# power_supply_module.net
KiCad netlist of a schematic drawn in EAGLE
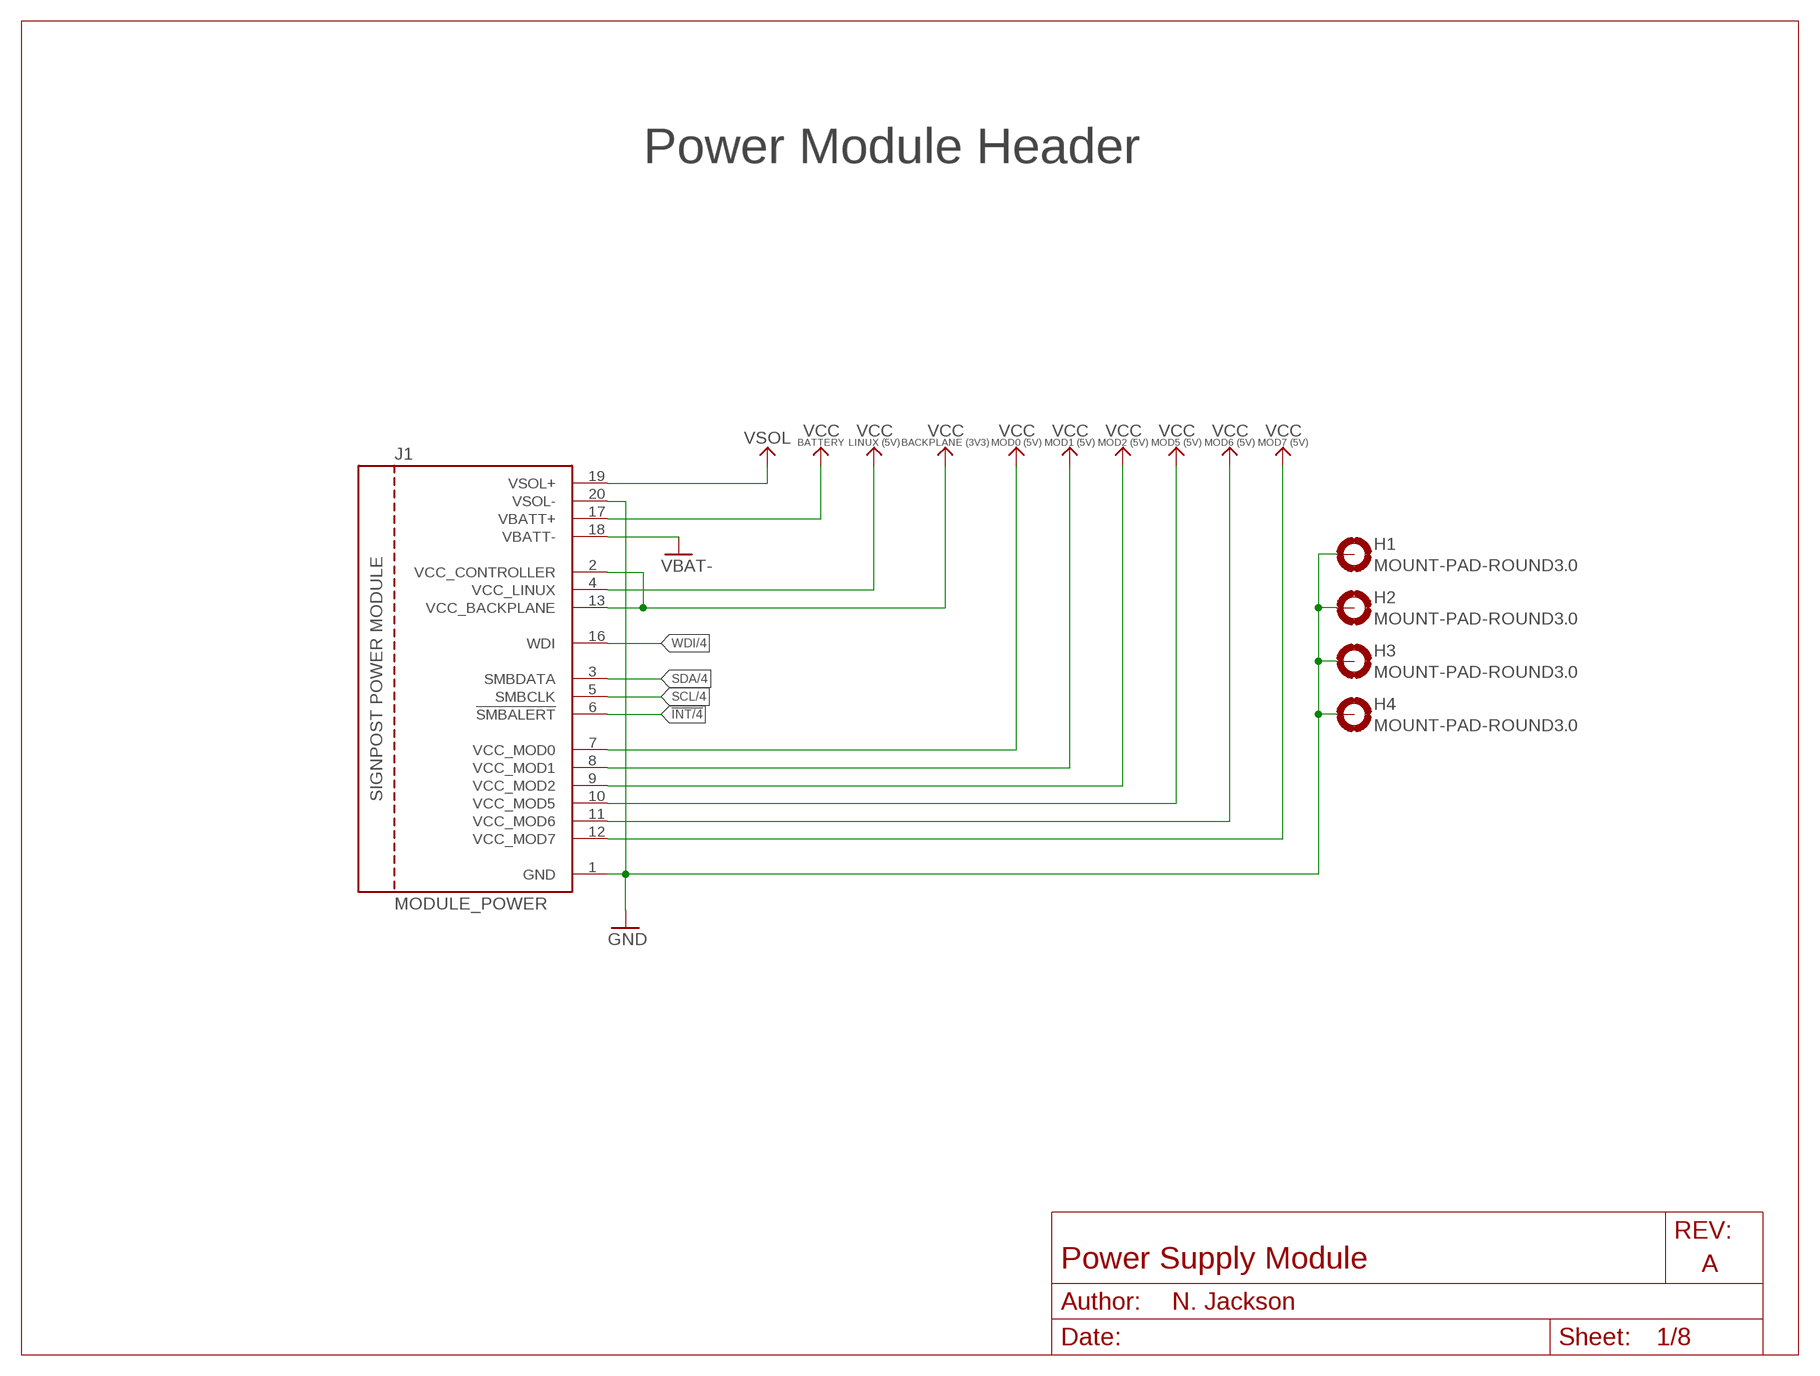
[diagram p0: schematic, sheet 1]
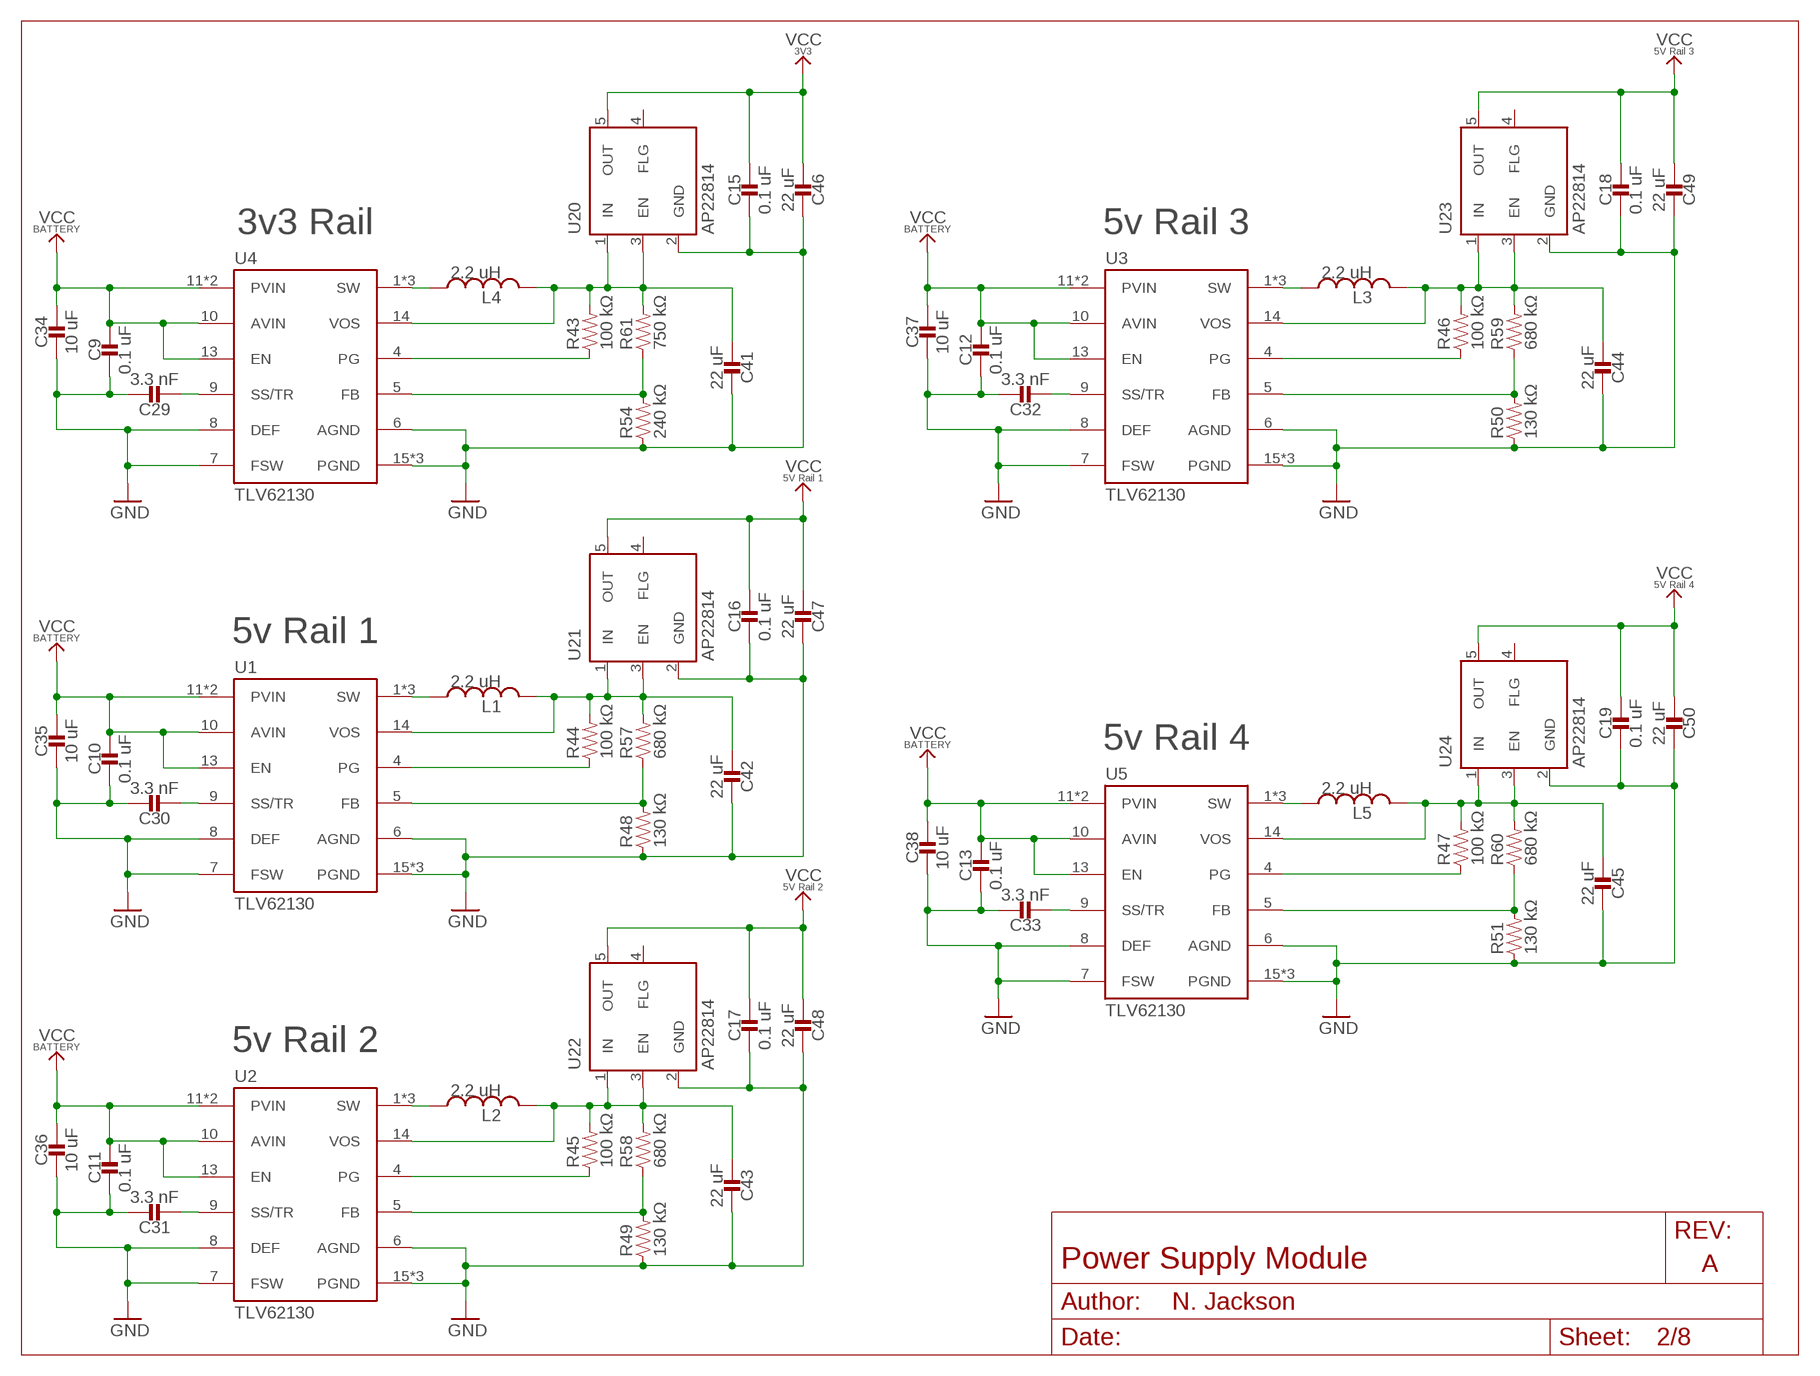
[diagram p1: schematic, sheet 2]
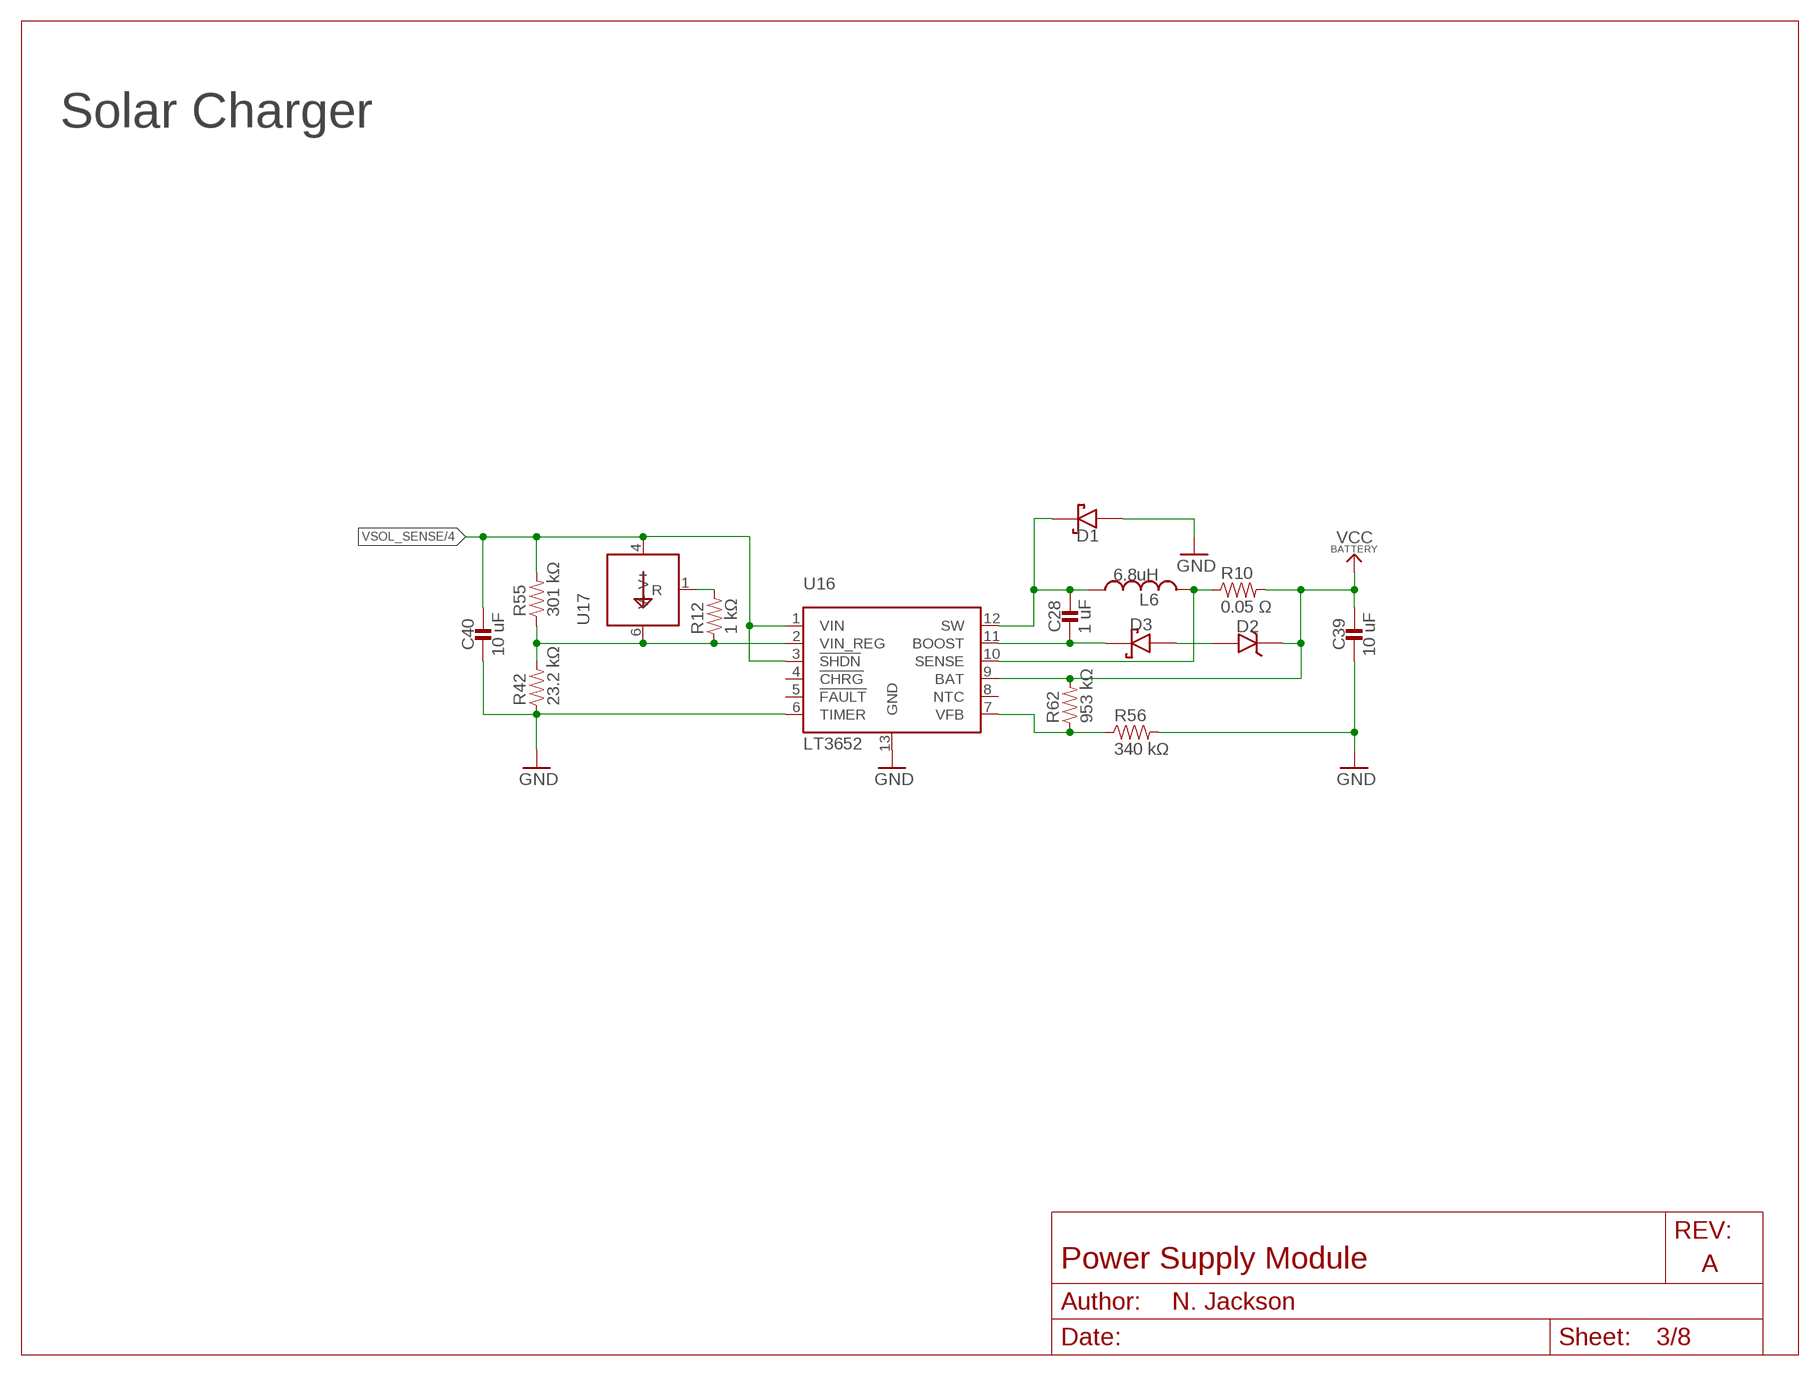
[diagram p2: schematic, sheet 3]
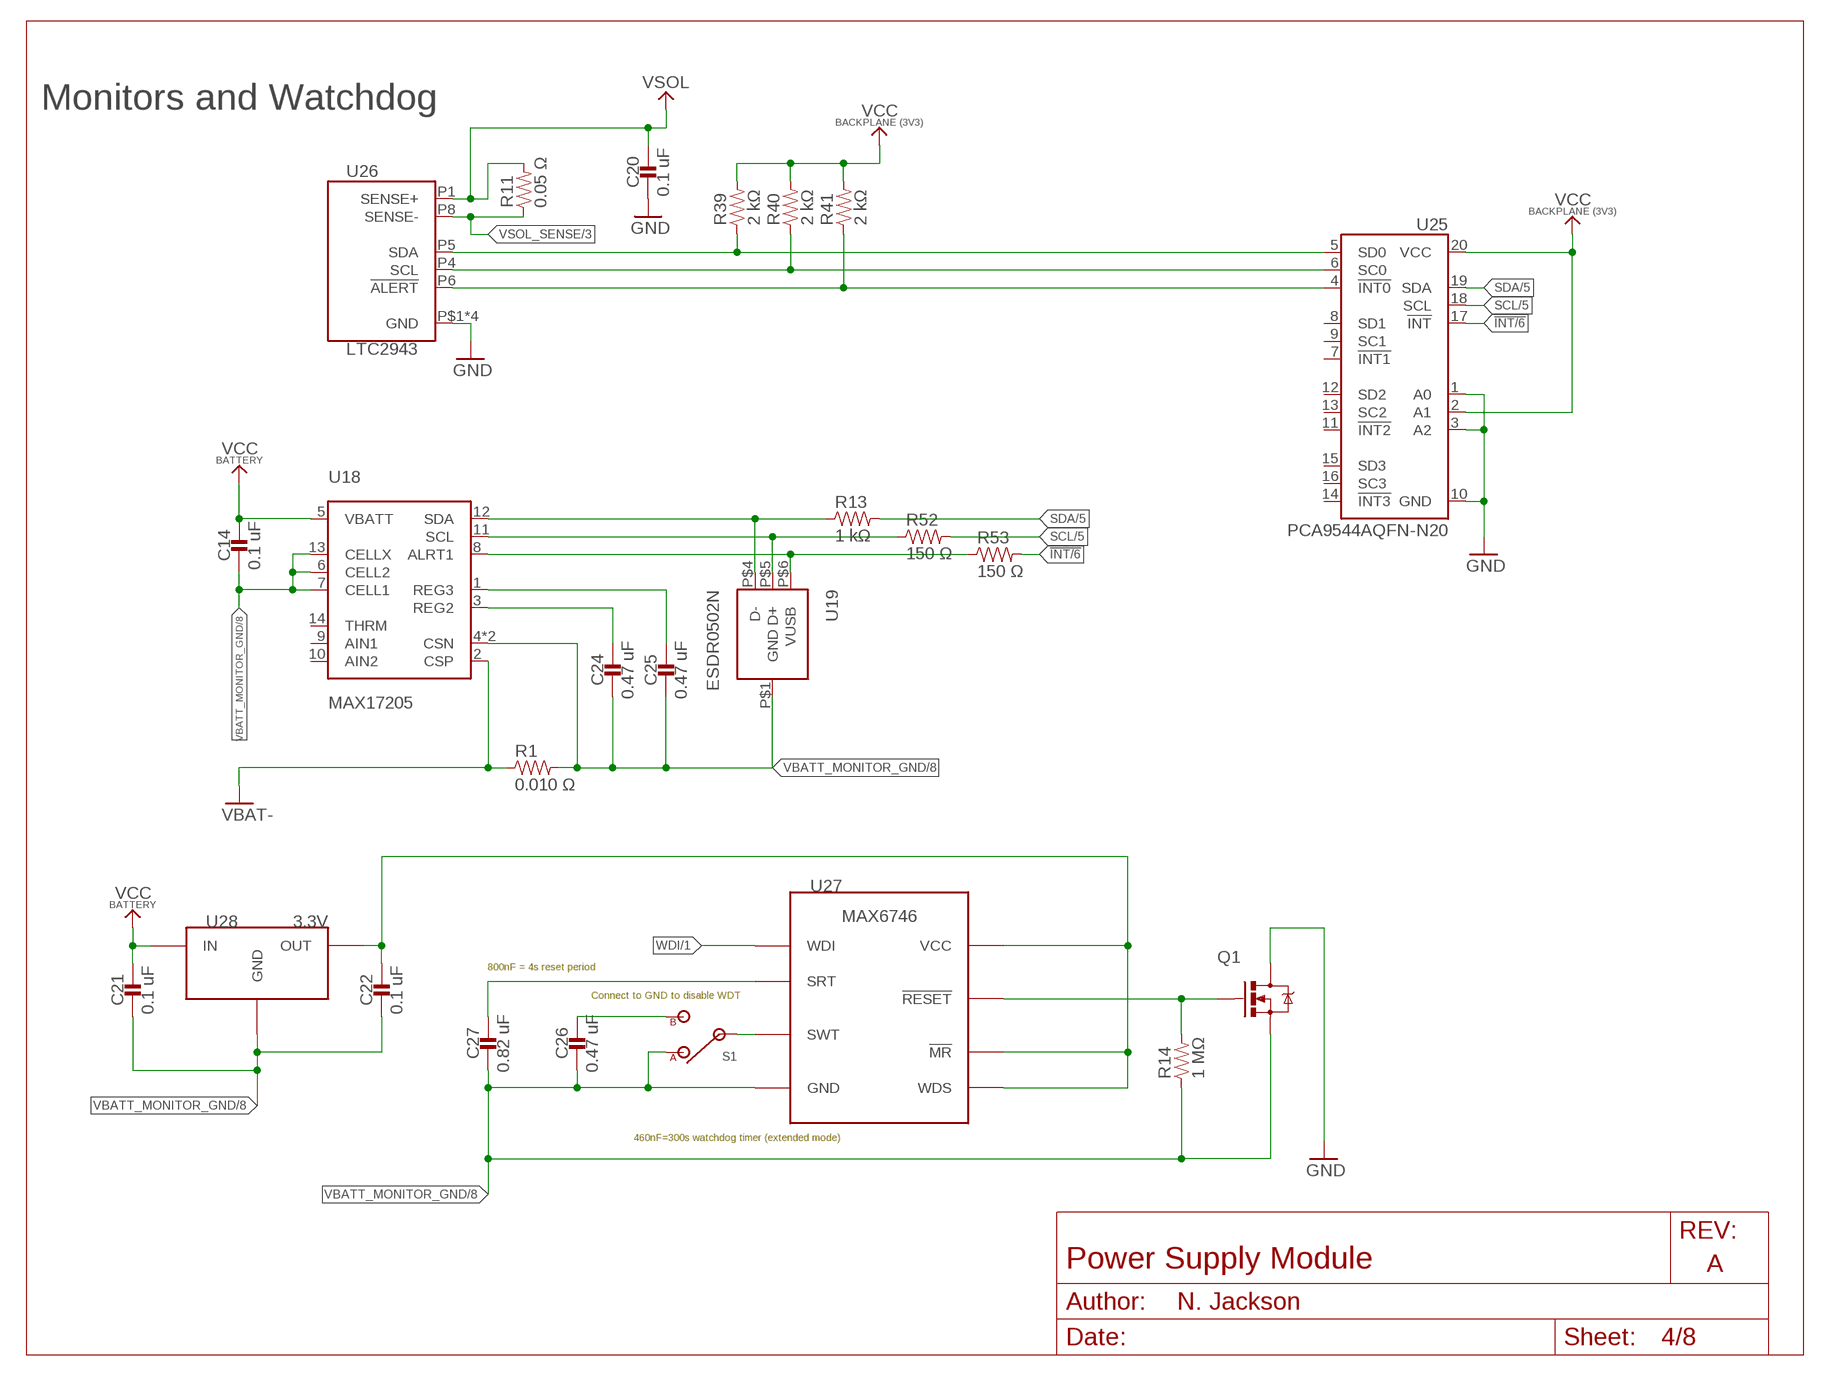
[diagram p3: schematic, sheet 4]
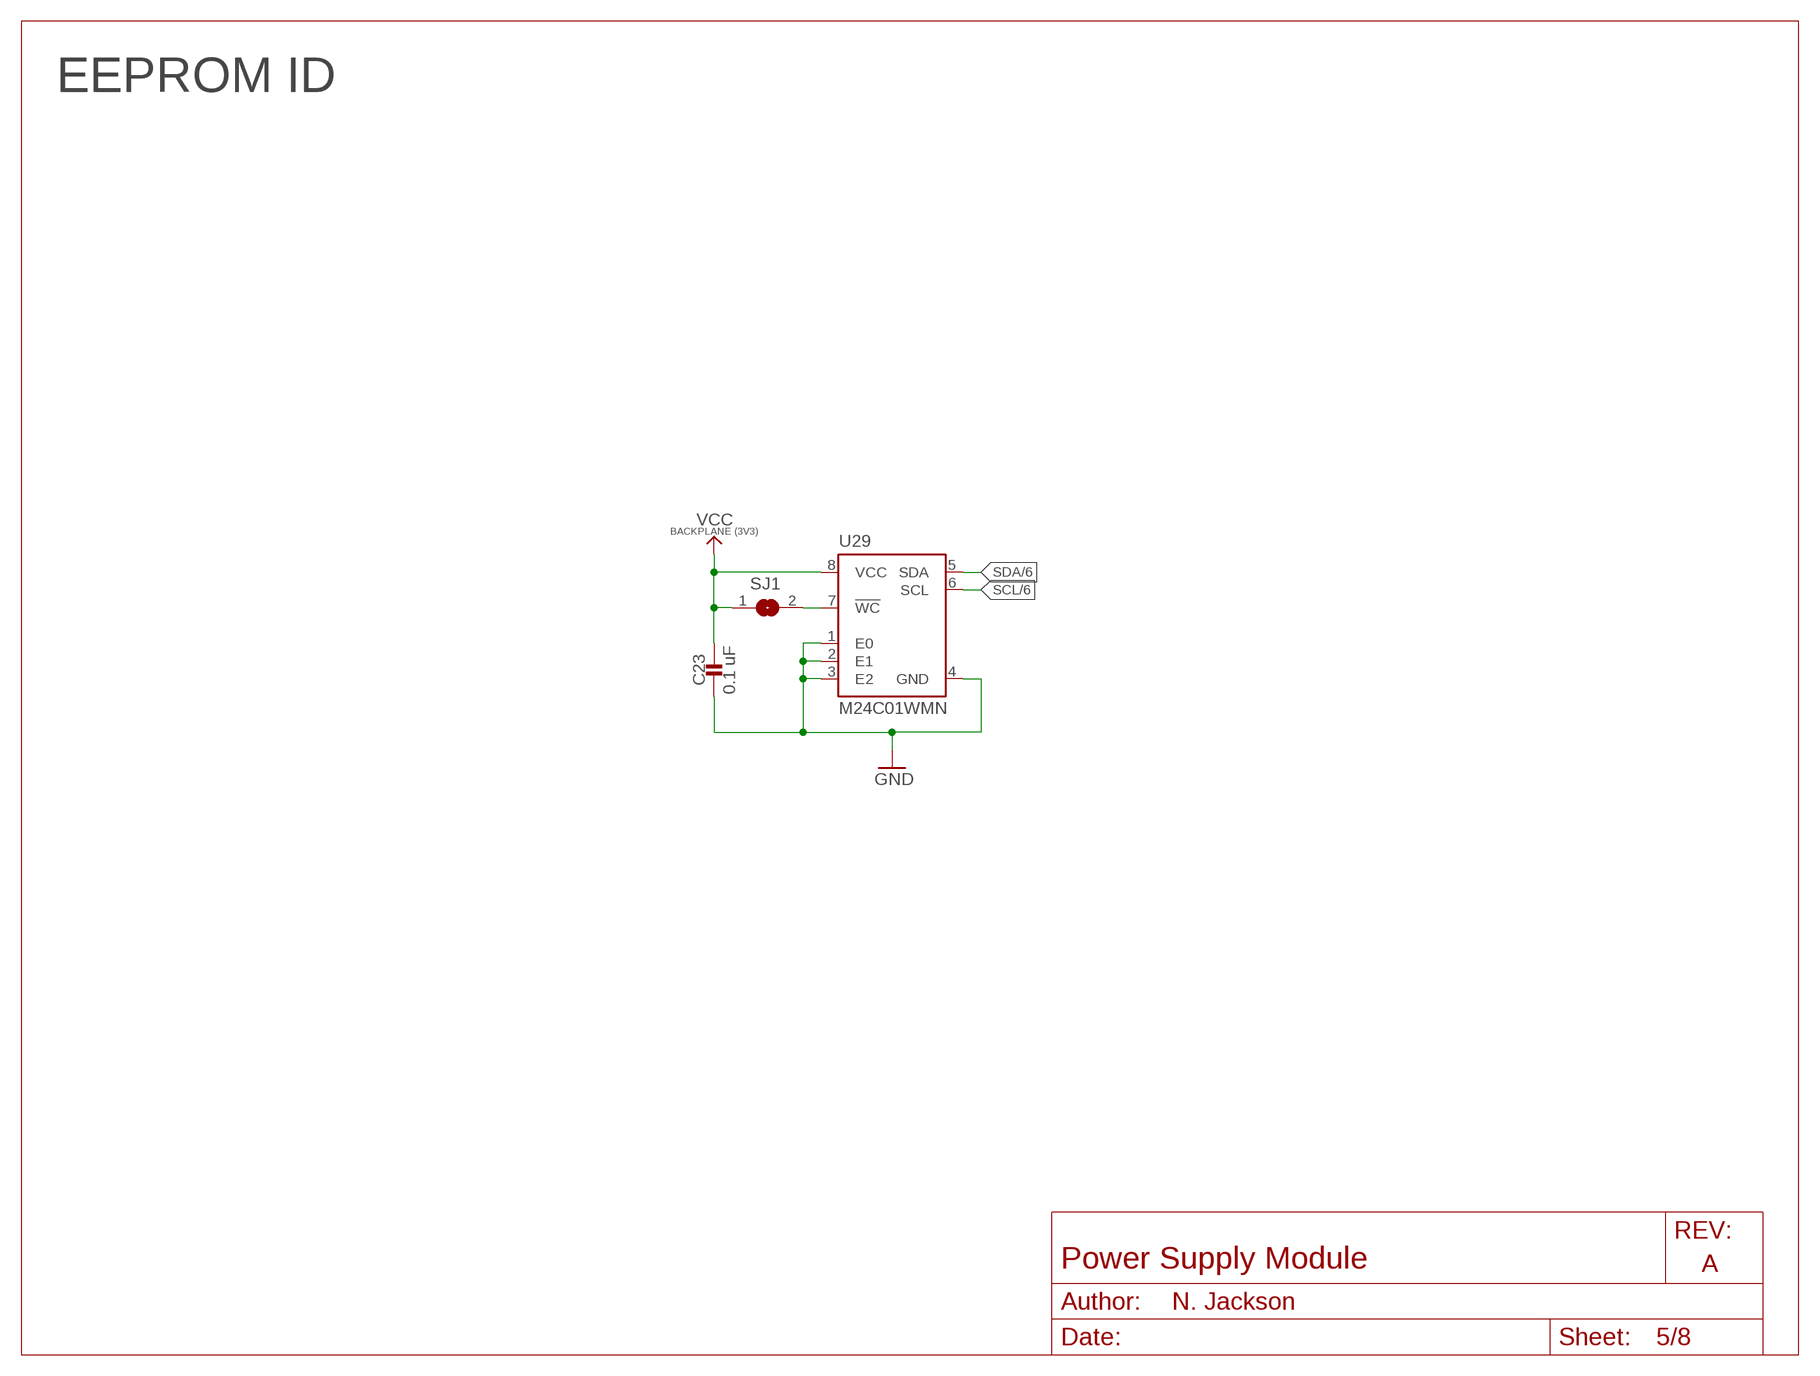
[diagram p4: schematic, sheet 5]
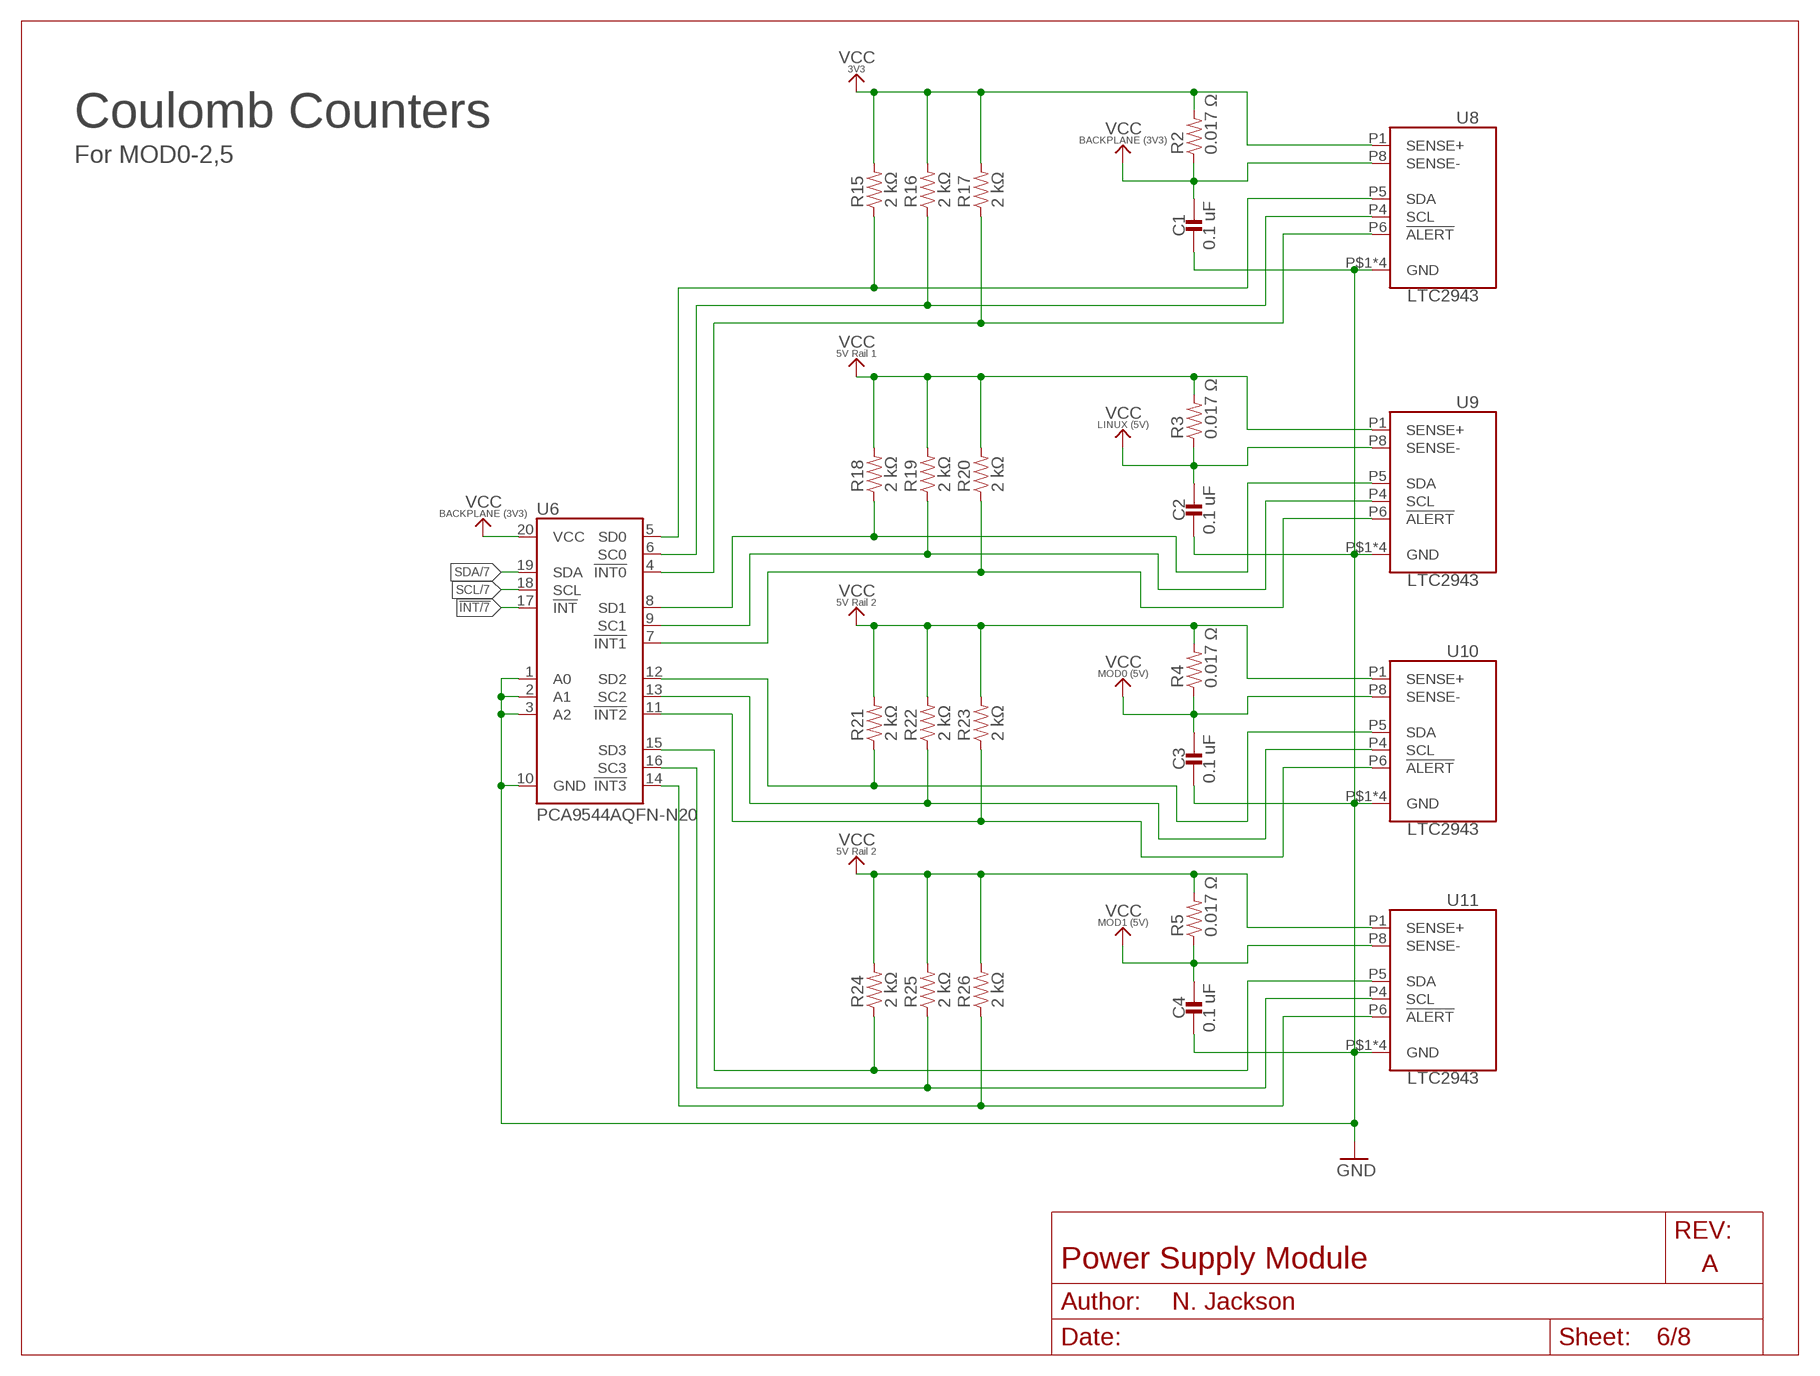
[diagram p5: schematic, sheet 6]
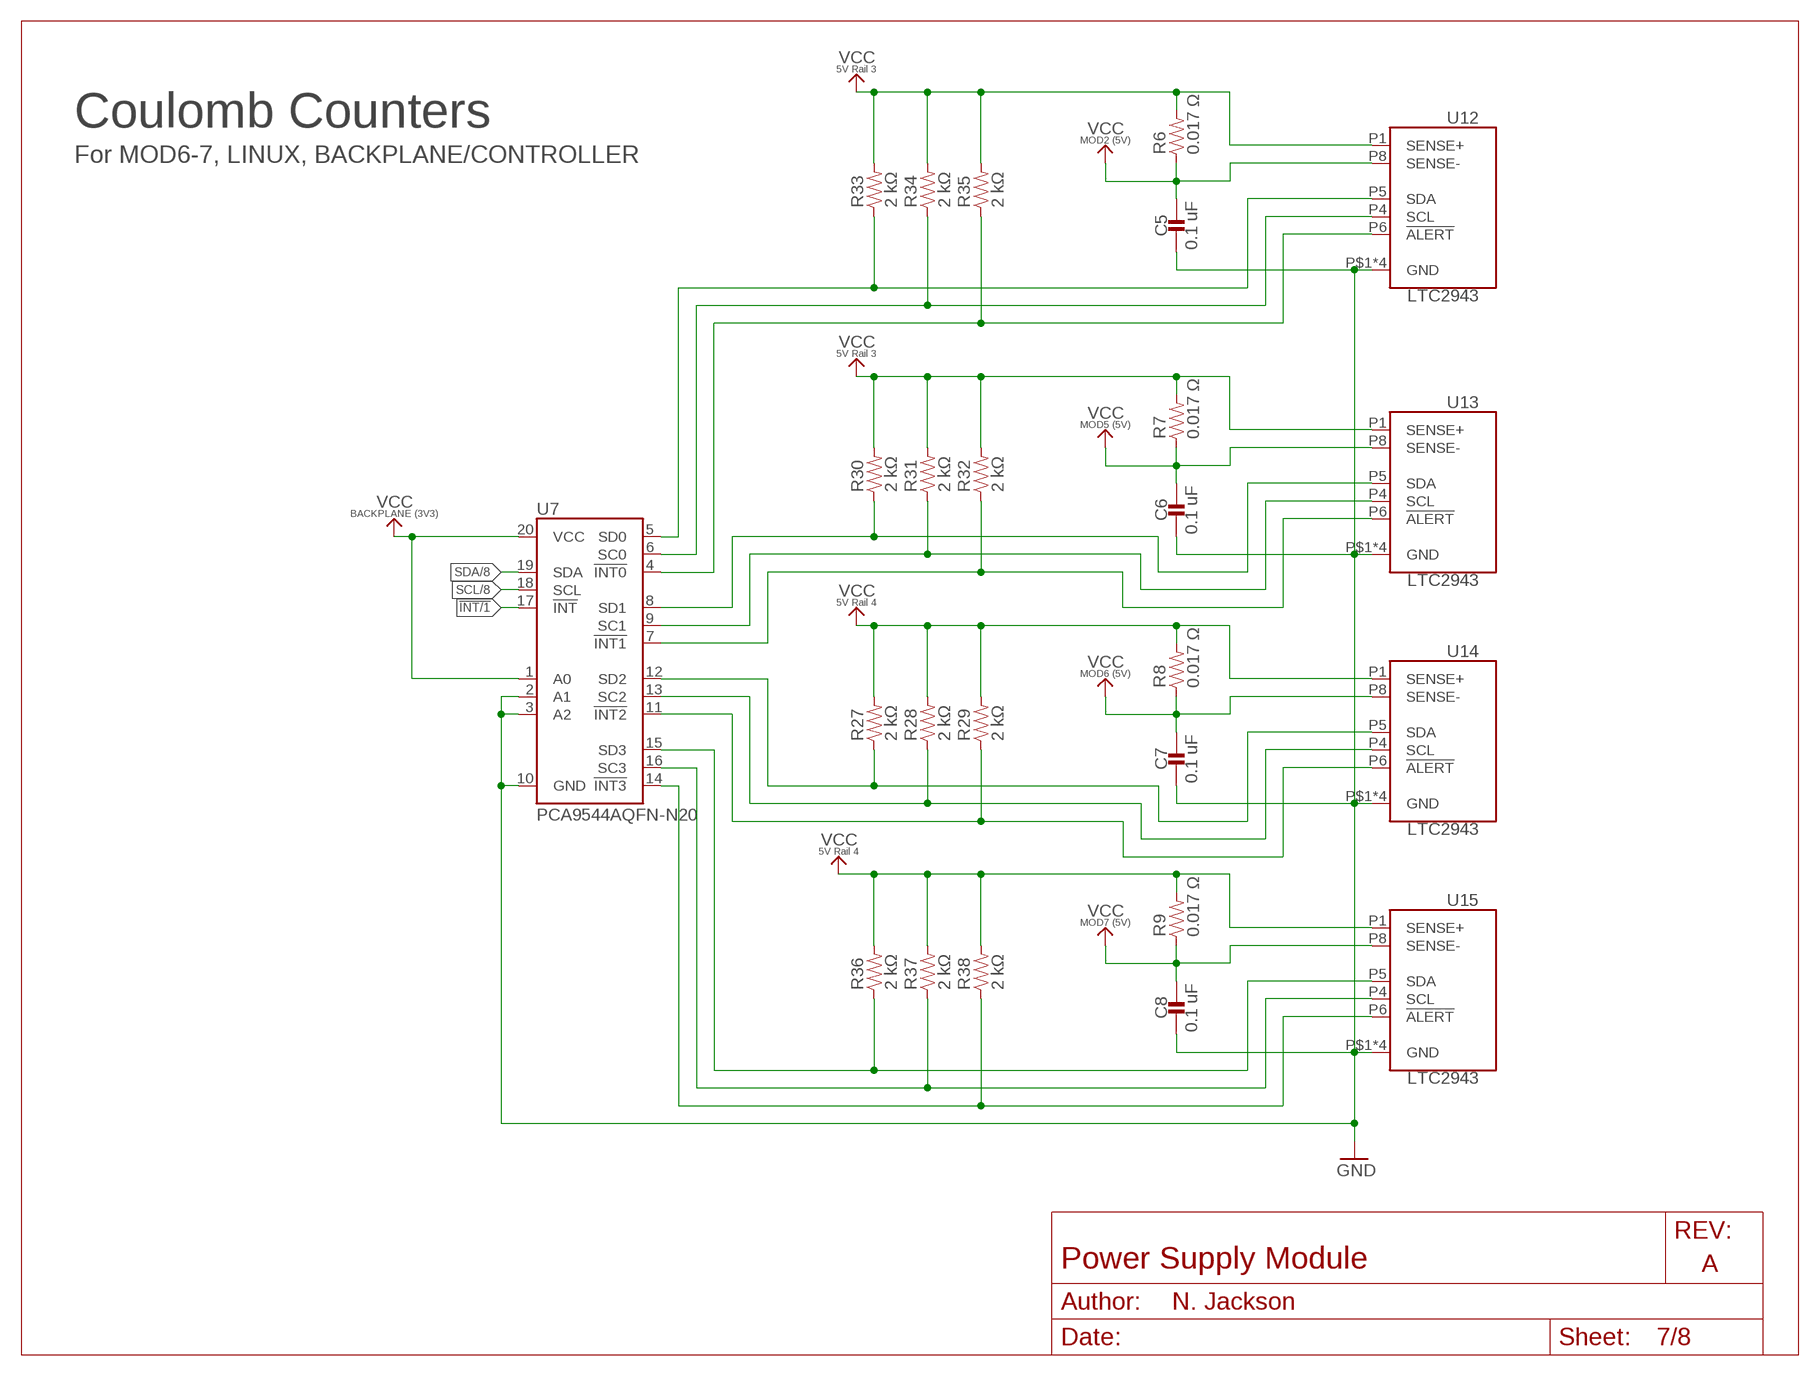
[diagram p6: schematic, sheet 7]
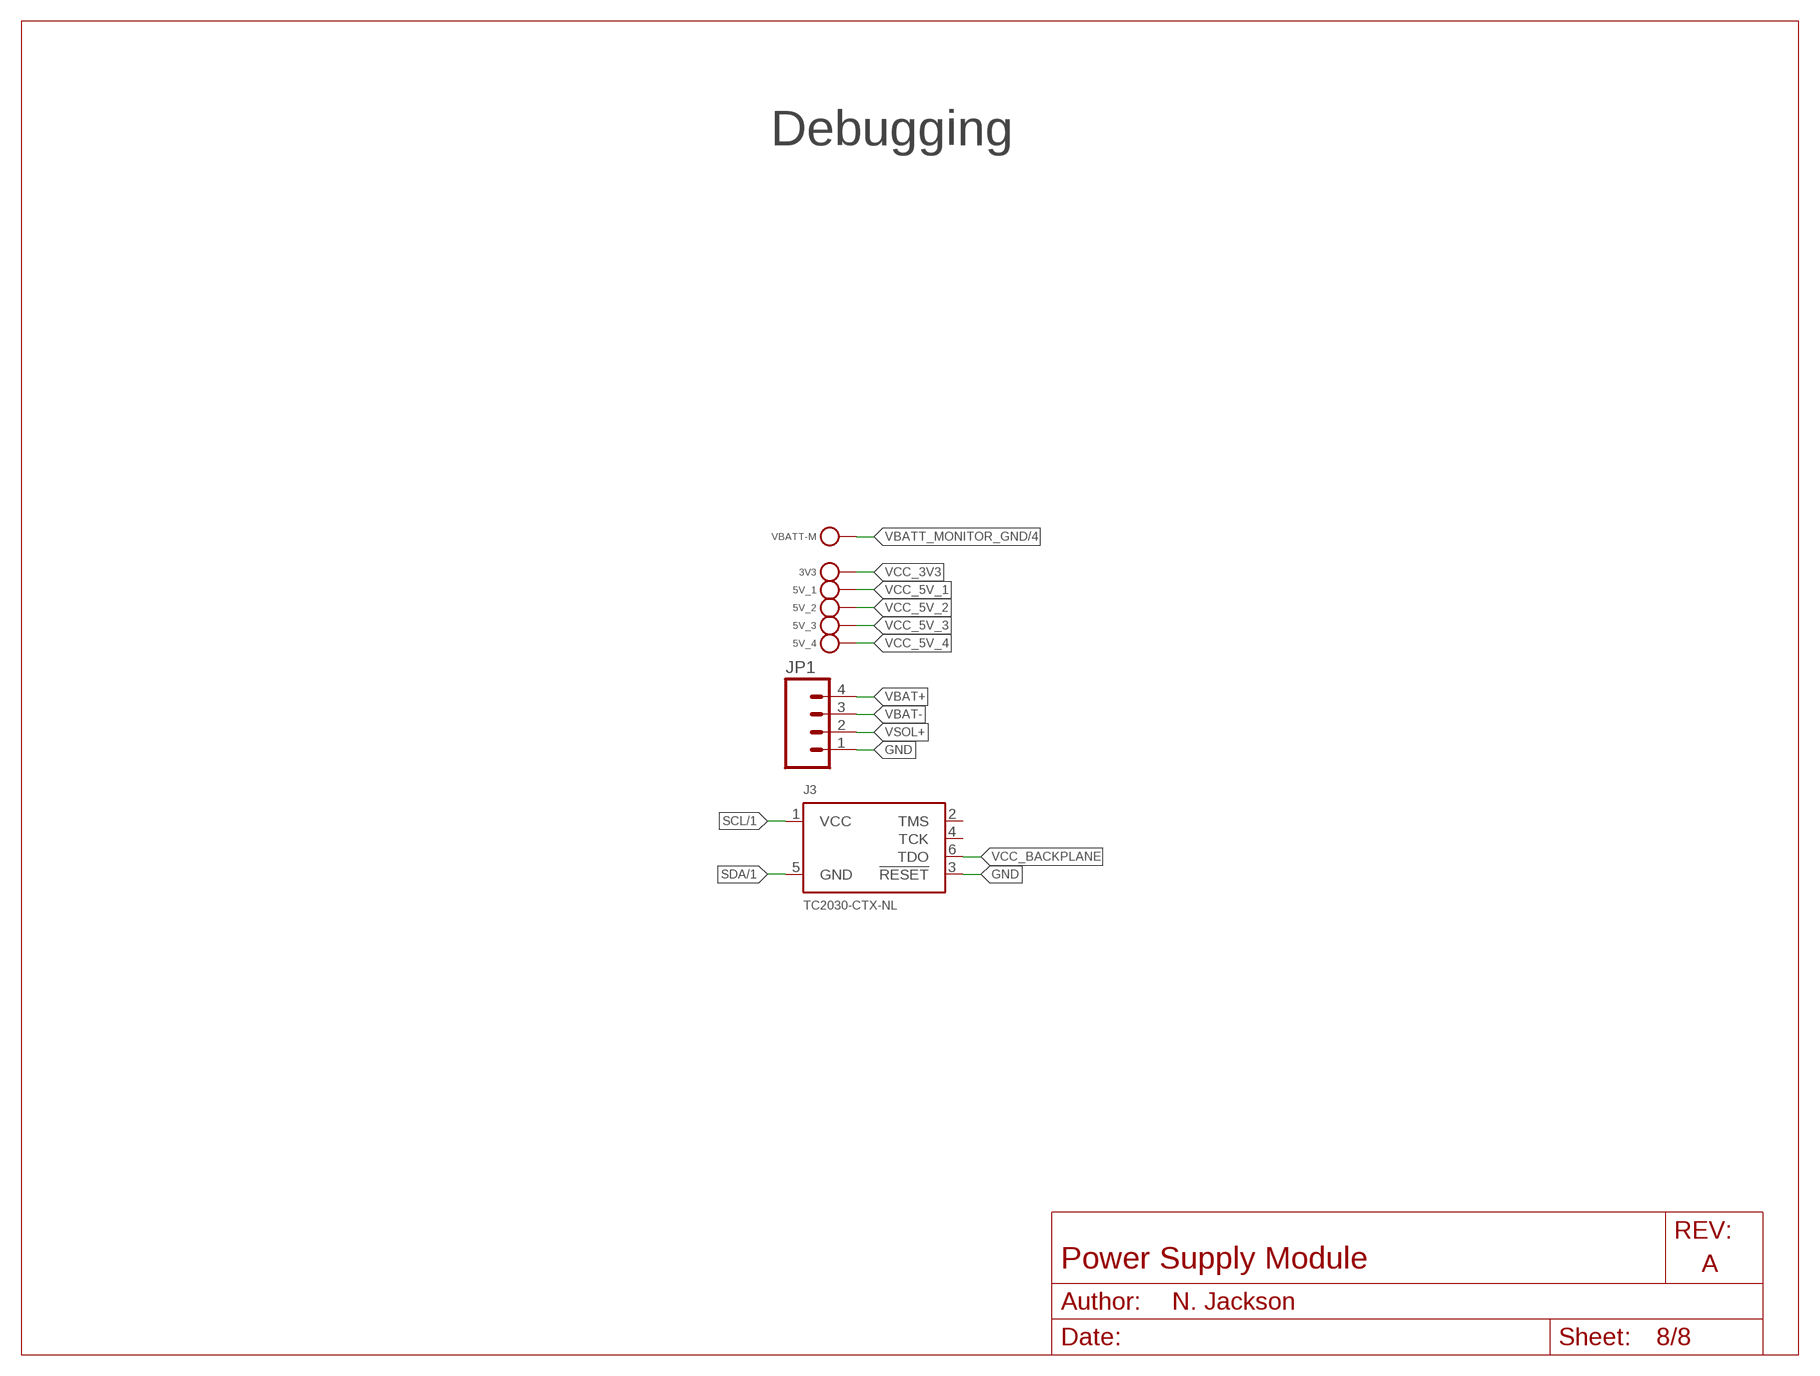
[diagram p7: schematic, sheet 8]

(export (version "E")
  (design (tool "Eeschema 10.0.6"))
  (components
    (comp (ref "C9")
      (value "0.1 uF")
      (footprint "eagle-import:0402_CAP")
      (libsource (lib "eagle-import") (part "CAPACITOR0402_CAP"))
    )
    (comp (ref "C10")
      (value "0.1 uF")
      (footprint "eagle-import:0402_CAP")
      (libsource (lib "eagle-import") (part "CAPACITOR0402_CAP"))
    )
    (comp (ref "C11")
      (value "0.1 uF")
      (footprint "eagle-import:0402_CAP")
      (libsource (lib "eagle-import") (part "CAPACITOR0402_CAP"))
    )
    (comp (ref "C12")
      (value "0.1 uF")
      (footprint "eagle-import:0402_CAP")
      (libsource (lib "eagle-import") (part "CAPACITOR0402_CAP"))
    )
    (comp (ref "C13")
      (value "0.1 uF")
      (footprint "eagle-import:0402_CAP")
      (libsource (lib "eagle-import") (part "CAPACITOR0402_CAP"))
    )
    (comp (ref "C15")
      (value "0.1 uF")
      (footprint "eagle-import:0402_CAP")
      (libsource (lib "eagle-import") (part "CAPACITOR0402_CAP"))
    )
    (comp (ref "C16")
      (value "0.1 uF")
      (footprint "eagle-import:0402_CAP")
      (libsource (lib "eagle-import") (part "CAPACITOR0402_CAP"))
    )
    (comp (ref "C17")
      (value "0.1 uF")
      (footprint "eagle-import:0402_CAP")
      (libsource (lib "eagle-import") (part "CAPACITOR0402_CAP"))
    )
    (comp (ref "C18")
      (value "0.1 uF")
      (footprint "eagle-import:0402_CAP")
      (libsource (lib "eagle-import") (part "CAPACITOR0402_CAP"))
    )
    (comp (ref "C19")
      (value "0.1 uF")
      (footprint "eagle-import:0402_CAP")
      (libsource (lib "eagle-import") (part "CAPACITOR0402_CAP"))
    )
    (comp (ref "C29")
      (value "3.3 nF")
      (footprint "eagle-import:0402_CAP")
      (libsource (lib "eagle-import") (part "CAPACITOR0402_CAP"))
    )
    (comp (ref "C30")
      (value "3.3 nF")
      (footprint "eagle-import:0402_CAP")
      (libsource (lib "eagle-import") (part "CAPACITOR0402_CAP"))
    )
    (comp (ref "C31")
      (value "3.3 nF")
      (footprint "eagle-import:0402_CAP")
      (libsource (lib "eagle-import") (part "CAPACITOR0402_CAP"))
    )
    (comp (ref "C32")
      (value "3.3 nF")
      (footprint "eagle-import:0402_CAP")
      (libsource (lib "eagle-import") (part "CAPACITOR0402_CAP"))
    )
    (comp (ref "C33")
      (value "3.3 nF")
      (footprint "eagle-import:0402_CAP")
      (libsource (lib "eagle-import") (part "CAPACITOR0402_CAP"))
    )
    (comp (ref "C34")
      (value "10 uF")
      (footprint "eagle-import:0805_CAP")
      (libsource (lib "eagle-import") (part "CAPACITOR0805_CAP"))
    )
    (comp (ref "C35")
      (value "10 uF")
      (footprint "eagle-import:0805_CAP")
      (libsource (lib "eagle-import") (part "CAPACITOR0805_CAP"))
    )
    (comp (ref "C36")
      (value "10 uF")
      (footprint "eagle-import:0805_CAP")
      (libsource (lib "eagle-import") (part "CAPACITOR0805_CAP"))
    )
    (comp (ref "C37")
      (value "10 uF")
      (footprint "eagle-import:0805_CAP")
      (libsource (lib "eagle-import") (part "CAPACITOR0805_CAP"))
    )
    (comp (ref "C38")
      (value "10 uF")
      (footprint "eagle-import:0805_CAP")
      (libsource (lib "eagle-import") (part "CAPACITOR0805_CAP"))
    )
    (comp (ref "C41")
      (value "22 uF")
      (footprint "eagle-import:0603_CAP")
      (libsource (lib "eagle-import") (part "CAPACITOR0603_CAP"))
    )
    (comp (ref "C42")
      (value "22 uF")
      (footprint "eagle-import:0603_CAP")
      (libsource (lib "eagle-import") (part "CAPACITOR0603_CAP"))
    )
    (comp (ref "C43")
      (value "22 uF")
      (footprint "eagle-import:0603_CAP")
      (libsource (lib "eagle-import") (part "CAPACITOR0603_CAP"))
    )
    (comp (ref "C44")
      (value "22 uF")
      (footprint "eagle-import:0603_CAP")
      (libsource (lib "eagle-import") (part "CAPACITOR0603_CAP"))
    )
    (comp (ref "C45")
      (value "22 uF")
      (footprint "eagle-import:0603_CAP")
      (libsource (lib "eagle-import") (part "CAPACITOR0603_CAP"))
    )
    (comp (ref "C46")
      (value "22 uF")
      (footprint "eagle-import:0603_CAP")
      (libsource (lib "eagle-import") (part "CAPACITOR0603_CAP"))
    )
    (comp (ref "C47")
      (value "22 uF")
      (footprint "eagle-import:0603_CAP")
      (libsource (lib "eagle-import") (part "CAPACITOR0603_CAP"))
    )
    (comp (ref "C48")
      (value "22 uF")
      (footprint "eagle-import:0603_CAP")
      (libsource (lib "eagle-import") (part "CAPACITOR0603_CAP"))
    )
    (comp (ref "C49")
      (value "22 uF")
      (footprint "eagle-import:0603_CAP")
      (libsource (lib "eagle-import") (part "CAPACITOR0603_CAP"))
    )
    (comp (ref "C50")
      (value "22 uF")
      (footprint "eagle-import:0603_CAP")
      (libsource (lib "eagle-import") (part "CAPACITOR0603_CAP"))
    )
    (comp (ref "L1")
      (value "2.2 uH")
      (footprint "eagle-import:IHL-1212BZ-11")
      (libsource (lib "eagle-import") (part "INDUCTORIHL"))
    )
    (comp (ref "L2")
      (value "2.2 uH")
      (footprint "eagle-import:IHL-1212BZ-11")
      (libsource (lib "eagle-import") (part "INDUCTORIHL"))
    )
    (comp (ref "L3")
      (value "2.2 uH")
      (footprint "eagle-import:IHL-1212BZ-11")
      (libsource (lib "eagle-import") (part "INDUCTORIHL"))
    )
    (comp (ref "L4")
      (value "2.2 uH")
      (footprint "eagle-import:IHL-1212BZ-11")
      (libsource (lib "eagle-import") (part "INDUCTORIHL"))
    )
    (comp (ref "L5")
      (value "2.2 uH")
      (footprint "eagle-import:IHL-1212BZ-11")
      (libsource (lib "eagle-import") (part "INDUCTORIHL"))
    )
    (comp (ref "R43")
      (value "100 kΩ")
      (footprint "eagle-import:0402_RES")
      (libsource (lib "eagle-import") (part "RESISTOR0402_RES"))
    )
    (comp (ref "R44")
      (value "100 kΩ")
      (footprint "eagle-import:0402_RES")
      (libsource (lib "eagle-import") (part "RESISTOR0402_RES"))
    )
    (comp (ref "R45")
      (value "100 kΩ")
      (footprint "eagle-import:0402_RES")
      (libsource (lib "eagle-import") (part "RESISTOR0402_RES"))
    )
    (comp (ref "R46")
      (value "100 kΩ")
      (footprint "eagle-import:0402_RES")
      (libsource (lib "eagle-import") (part "RESISTOR0402_RES"))
    )
    (comp (ref "R47")
      (value "100 kΩ")
      (footprint "eagle-import:0402_RES")
      (libsource (lib "eagle-import") (part "RESISTOR0402_RES"))
    )
    (comp (ref "R48")
      (value "130 kΩ")
      (footprint "eagle-import:0402_RES")
      (libsource (lib "eagle-import") (part "RESISTOR0402_RES"))
    )
    (comp (ref "R49")
      (value "130 kΩ")
      (footprint "eagle-import:0402_RES")
      (libsource (lib "eagle-import") (part "RESISTOR0402_RES"))
    )
    (comp (ref "R50")
      (value "130 kΩ")
      (footprint "eagle-import:0402_RES")
      (libsource (lib "eagle-import") (part "RESISTOR0402_RES"))
    )
    (comp (ref "R51")
      (value "130 kΩ")
      (footprint "eagle-import:0402_RES")
      (libsource (lib "eagle-import") (part "RESISTOR0402_RES"))
    )
    (comp (ref "R54")
      (value "240 kΩ")
      (footprint "eagle-import:0402_RES")
      (libsource (lib "eagle-import") (part "RESISTOR0402_RES"))
    )
    (comp (ref "R57")
      (value "680 kΩ")
      (footprint "eagle-import:0402_RES")
      (libsource (lib "eagle-import") (part "RESISTOR0402_RES"))
    )
    (comp (ref "R58")
      (value "680 kΩ")
      (footprint "eagle-import:0402_RES")
      (libsource (lib "eagle-import") (part "RESISTOR0402_RES"))
    )
    (comp (ref "R59")
      (value "680 kΩ")
      (footprint "eagle-import:0402_RES")
      (libsource (lib "eagle-import") (part "RESISTOR0402_RES"))
    )
    (comp (ref "R60")
      (value "680 kΩ")
      (footprint "eagle-import:0402_RES")
      (libsource (lib "eagle-import") (part "RESISTOR0402_RES"))
    )
    (comp (ref "R61")
      (value "750 kΩ")
      (footprint "eagle-import:0402_RES")
      (libsource (lib "eagle-import") (part "RESISTOR0402_RES"))
    )
    (comp (ref "U1")
      (value "TLV62130")
      (footprint "eagle-import:TQFN-16_3MM")
      (libsource (lib "eagle-import") (part "TLV62130"))
    )
    (comp (ref "U2")
      (value "TLV62130")
      (footprint "eagle-import:TQFN-16_3MM")
      (libsource (lib "eagle-import") (part "TLV62130"))
    )
    (comp (ref "U3")
      (value "TLV62130")
      (footprint "eagle-import:TQFN-16_3MM")
      (libsource (lib "eagle-import") (part "TLV62130"))
    )
    (comp (ref "U4")
      (value "TLV62130")
      (footprint "eagle-import:TQFN-16_3MM")
      (libsource (lib "eagle-import") (part "TLV62130"))
    )
    (comp (ref "U5")
      (value "TLV62130")
      (footprint "eagle-import:TQFN-16_3MM")
      (libsource (lib "eagle-import") (part "TLV62130"))
    )
    (comp (ref "U20")
      (value "AP22814")
      (footprint "eagle-import:U-DFN2020-6")
      (libsource (lib "eagle-import") (part "AP22814"))
    )
    (comp (ref "U21")
      (value "AP22814")
      (footprint "eagle-import:U-DFN2020-6")
      (libsource (lib "eagle-import") (part "AP22814"))
    )
    (comp (ref "U22")
      (value "AP22814")
      (footprint "eagle-import:U-DFN2020-6")
      (libsource (lib "eagle-import") (part "AP22814"))
    )
    (comp (ref "U23")
      (value "AP22814")
      (footprint "eagle-import:U-DFN2020-6")
      (libsource (lib "eagle-import") (part "AP22814"))
    )
    (comp (ref "U24")
      (value "AP22814")
      (footprint "eagle-import:U-DFN2020-6")
      (libsource (lib "eagle-import") (part "AP22814"))
    )
    (comp (ref "C1")
      (value "0.1 uF")
      (footprint "eagle-import:0402_CAP")
      (libsource (lib "eagle-import") (part "CAPACITOR0402_CAP"))
    )
    (comp (ref "C2")
      (value "0.1 uF")
      (footprint "eagle-import:0402_CAP")
      (libsource (lib "eagle-import") (part "CAPACITOR0402_CAP"))
    )
    (comp (ref "C3")
      (value "0.1 uF")
      (footprint "eagle-import:0402_CAP")
      (libsource (lib "eagle-import") (part "CAPACITOR0402_CAP"))
    )
    (comp (ref "C4")
      (value "0.1 uF")
      (footprint "eagle-import:0402_CAP")
      (libsource (lib "eagle-import") (part "CAPACITOR0402_CAP"))
    )
    (comp (ref "R2")
      (value "0.017 Ω")
      (footprint "eagle-import:0805_RES")
      (libsource (lib "eagle-import") (part "RESISTOR0805_RES"))
    )
    (comp (ref "R3")
      (value "0.017 Ω")
      (footprint "eagle-import:0805_RES")
      (libsource (lib "eagle-import") (part "RESISTOR0805_RES"))
    )
    (comp (ref "R4")
      (value "0.017 Ω")
      (footprint "eagle-import:0805_RES")
      (libsource (lib "eagle-import") (part "RESISTOR0805_RES"))
    )
    (comp (ref "R5")
      (value "0.017 Ω")
      (footprint "eagle-import:0805_RES")
      (libsource (lib "eagle-import") (part "RESISTOR0805_RES"))
    )
    (comp (ref "R15")
      (value "2 kΩ")
      (footprint "eagle-import:0402_RES")
      (libsource (lib "eagle-import") (part "RESISTOR0402_RES"))
    )
    (comp (ref "R16")
      (value "2 kΩ")
      (footprint "eagle-import:0402_RES")
      (libsource (lib "eagle-import") (part "RESISTOR0402_RES"))
    )
    (comp (ref "R17")
      (value "2 kΩ")
      (footprint "eagle-import:0402_RES")
      (libsource (lib "eagle-import") (part "RESISTOR0402_RES"))
    )
    (comp (ref "R18")
      (value "2 kΩ")
      (footprint "eagle-import:0402_RES")
      (libsource (lib "eagle-import") (part "RESISTOR0402_RES"))
    )
    (comp (ref "R19")
      (value "2 kΩ")
      (footprint "eagle-import:0402_RES")
      (libsource (lib "eagle-import") (part "RESISTOR0402_RES"))
    )
    (comp (ref "R20")
      (value "2 kΩ")
      (footprint "eagle-import:0402_RES")
      (libsource (lib "eagle-import") (part "RESISTOR0402_RES"))
    )
    (comp (ref "R21")
      (value "2 kΩ")
      (footprint "eagle-import:0402_RES")
      (libsource (lib "eagle-import") (part "RESISTOR0402_RES"))
    )
    (comp (ref "R22")
      (value "2 kΩ")
      (footprint "eagle-import:0402_RES")
      (libsource (lib "eagle-import") (part "RESISTOR0402_RES"))
    )
    (comp (ref "R23")
      (value "2 kΩ")
      (footprint "eagle-import:0402_RES")
      (libsource (lib "eagle-import") (part "RESISTOR0402_RES"))
    )
    (comp (ref "R24")
      (value "2 kΩ")
      (footprint "eagle-import:0402_RES")
      (libsource (lib "eagle-import") (part "RESISTOR0402_RES"))
    )
    (comp (ref "R25")
      (value "2 kΩ")
      (footprint "eagle-import:0402_RES")
      (libsource (lib "eagle-import") (part "RESISTOR0402_RES"))
    )
    (comp (ref "R26")
      (value "2 kΩ")
      (footprint "eagle-import:0402_RES")
      (libsource (lib "eagle-import") (part "RESISTOR0402_RES"))
    )
    (comp (ref "U6")
      (value "PCA9544AQFN-N20")
      (footprint "eagle-import:QFN-N20")
      (libsource (lib "eagle-import") (part "PCA9544AQFN-N20"))
    )
    (comp (ref "U8")
      (value "LTC2943")
      (footprint "eagle-import:DFN-8")
      (libsource (lib "eagle-import") (part "LTC2943"))
    )
    (comp (ref "U9")
      (value "LTC2943")
      (footprint "eagle-import:DFN-8")
      (libsource (lib "eagle-import") (part "LTC2943"))
    )
    (comp (ref "U10")
      (value "LTC2943")
      (footprint "eagle-import:DFN-8")
      (libsource (lib "eagle-import") (part "LTC2943"))
    )
    (comp (ref "U11")
      (value "LTC2943")
      (footprint "eagle-import:DFN-8")
      (libsource (lib "eagle-import") (part "LTC2943"))
    )
    (comp (ref "3V3")
      (value "TEST_POINT_0.040IN")
      (footprint "eagle-import:TESTPOINT_0.040IN")
      (libsource (lib "eagle-import") (part "TEST_POINT_0.040IN"))
    )
    (comp (ref "5V_1")
      (value "TEST_POINT_0.040IN")
      (footprint "eagle-import:TESTPOINT_0.040IN")
      (libsource (lib "eagle-import") (part "TEST_POINT_0.040IN"))
    )
    (comp (ref "5V_2")
      (value "TEST_POINT_0.040IN")
      (footprint "eagle-import:TESTPOINT_0.040IN")
      (libsource (lib "eagle-import") (part "TEST_POINT_0.040IN"))
    )
    (comp (ref "5V_3")
      (value "TEST_POINT_0.040IN")
      (footprint "eagle-import:TESTPOINT_0.040IN")
      (libsource (lib "eagle-import") (part "TEST_POINT_0.040IN"))
    )
    (comp (ref "5V_4")
      (value "TEST_POINT_0.040IN")
      (footprint "eagle-import:TESTPOINT_0.040IN")
      (libsource (lib "eagle-import") (part "TEST_POINT_0.040IN"))
    )
    (comp (ref "J3")
      (value "TC2030-CTX-NL")
      (footprint "eagle-import:TC2030-IDC-NL")
      (libsource (lib "eagle-import") (part "TC2030-CTX-NL"))
    )
    (comp (ref "JP1")
      (value "M04PTH")
      (footprint "eagle-import:1X04")
      (libsource (lib "eagle-import") (part "M04PTH"))
    )
    (comp (ref "VBATT-M")
      (value "TEST_POINT_0.040IN")
      (footprint "eagle-import:TESTPOINT_0.040IN")
      (libsource (lib "eagle-import") (part "TEST_POINT_0.040IN"))
    )
    (comp (ref "C23")
      (value "0.1 uF")
      (footprint "eagle-import:0402_CAP")
      (libsource (lib "eagle-import") (part "CAPACITOR0402_CAP"))
    )
    (comp (ref "SJ1") (value "SJ") (footprint "eagle-import:SJ") (libsource (lib "eagle-import") (part "SJ")))
    (comp (ref "U29")
      (value "M24C01WMN")
      (footprint "eagle-import:SOIC-8")
      (libsource (lib "eagle-import") (part "M24C01WMN"))
    )
    (comp (ref "C5")
      (value "0.1 uF")
      (footprint "eagle-import:0402_CAP")
      (libsource (lib "eagle-import") (part "CAPACITOR0402_CAP"))
    )
    (comp (ref "C6")
      (value "0.1 uF")
      (footprint "eagle-import:0402_CAP")
      (libsource (lib "eagle-import") (part "CAPACITOR0402_CAP"))
    )
    (comp (ref "C7")
      (value "0.1 uF")
      (footprint "eagle-import:0402_CAP")
      (libsource (lib "eagle-import") (part "CAPACITOR0402_CAP"))
    )
    (comp (ref "C8")
      (value "0.1 uF")
      (footprint "eagle-import:0402_CAP")
      (libsource (lib "eagle-import") (part "CAPACITOR0402_CAP"))
    )
    (comp (ref "R6")
      (value "0.017 Ω")
      (footprint "eagle-import:0805_RES")
      (libsource (lib "eagle-import") (part "RESISTOR0805_RES"))
    )
    (comp (ref "R7")
      (value "0.017 Ω")
      (footprint "eagle-import:0805_RES")
      (libsource (lib "eagle-import") (part "RESISTOR0805_RES"))
    )
    (comp (ref "R8")
      (value "0.017 Ω")
      (footprint "eagle-import:0805_RES")
      (libsource (lib "eagle-import") (part "RESISTOR0805_RES"))
    )
    (comp (ref "R9")
      (value "0.017 Ω")
      (footprint "eagle-import:0805_RES")
      (libsource (lib "eagle-import") (part "RESISTOR0805_RES"))
    )
    (comp (ref "R27")
      (value "2 kΩ")
      (footprint "eagle-import:0402_RES")
      (libsource (lib "eagle-import") (part "RESISTOR0402_RES"))
    )
    (comp (ref "R28")
      (value "2 kΩ")
      (footprint "eagle-import:0402_RES")
      (libsource (lib "eagle-import") (part "RESISTOR0402_RES"))
    )
    (comp (ref "R29")
      (value "2 kΩ")
      (footprint "eagle-import:0402_RES")
      (libsource (lib "eagle-import") (part "RESISTOR0402_RES"))
    )
    (comp (ref "R30")
      (value "2 kΩ")
      (footprint "eagle-import:0402_RES")
      (libsource (lib "eagle-import") (part "RESISTOR0402_RES"))
    )
    (comp (ref "R31")
      (value "2 kΩ")
      (footprint "eagle-import:0402_RES")
      (libsource (lib "eagle-import") (part "RESISTOR0402_RES"))
    )
    (comp (ref "R32")
      (value "2 kΩ")
      (footprint "eagle-import:0402_RES")
      (libsource (lib "eagle-import") (part "RESISTOR0402_RES"))
    )
    (comp (ref "R33")
      (value "2 kΩ")
      (footprint "eagle-import:0402_RES")
      (libsource (lib "eagle-import") (part "RESISTOR0402_RES"))
    )
    (comp (ref "R34")
      (value "2 kΩ")
      (footprint "eagle-import:0402_RES")
      (libsource (lib "eagle-import") (part "RESISTOR0402_RES"))
    )
    (comp (ref "R35")
      (value "2 kΩ")
      (footprint "eagle-import:0402_RES")
      (libsource (lib "eagle-import") (part "RESISTOR0402_RES"))
    )
    (comp (ref "R36")
      (value "2 kΩ")
      (footprint "eagle-import:0402_RES")
      (libsource (lib "eagle-import") (part "RESISTOR0402_RES"))
    )
    (comp (ref "R37")
      (value "2 kΩ")
      (footprint "eagle-import:0402_RES")
      (libsource (lib "eagle-import") (part "RESISTOR0402_RES"))
    )
    (comp (ref "R38")
      (value "2 kΩ")
      (footprint "eagle-import:0402_RES")
      (libsource (lib "eagle-import") (part "RESISTOR0402_RES"))
    )
    (comp (ref "U7")
      (value "PCA9544AQFN-N20")
      (footprint "eagle-import:QFN-N20")
      (libsource (lib "eagle-import") (part "PCA9544AQFN-N20"))
    )
    (comp (ref "U12")
      (value "LTC2943")
      (footprint "eagle-import:DFN-8")
      (libsource (lib "eagle-import") (part "LTC2943"))
    )
    (comp (ref "U13")
      (value "LTC2943")
      (footprint "eagle-import:DFN-8")
      (libsource (lib "eagle-import") (part "LTC2943"))
    )
    (comp (ref "U14")
      (value "LTC2943")
      (footprint "eagle-import:DFN-8")
      (libsource (lib "eagle-import") (part "LTC2943"))
    )
    (comp (ref "U15")
      (value "LTC2943")
      (footprint "eagle-import:DFN-8")
      (libsource (lib "eagle-import") (part "LTC2943"))
    )
    (comp (ref "C28")
      (value "1 uF")
      (footprint "eagle-import:0603_CAP")
      (libsource (lib "eagle-import") (part "CAPACITOR0603_CAP"))
    )
    (comp (ref "C39")
      (value "10 uF")
      (footprint "eagle-import:0805_CAP")
      (libsource (lib "eagle-import") (part "CAPACITOR0805_CAP"))
    )
    (comp (ref "C40")
      (value "10 uF")
      (footprint "eagle-import:0805_CAP")
      (libsource (lib "eagle-import") (part "CAPACITOR0805_CAP"))
    )
    (comp (ref "D1")
      (value "DIODE_SCHOTTKYSOT-23F")
      (footprint "eagle-import:SOT-23F")
      (libsource (lib "eagle-import") (part "DIODE_SCHOTTKYSOT-23F"))
    )
    (comp (ref "D2")
      (value "DIODE_ZENERSOT323")
      (footprint "eagle-import:SOD323")
      (libsource (lib "eagle-import") (part "DIODE_ZENERSOT323"))
    )
    (comp (ref "D3")
      (value "DIODE_SCHOTTKYSOT-23F")
      (footprint "eagle-import:SOT-23F")
      (libsource (lib "eagle-import") (part "DIODE_SCHOTTKYSOT-23F"))
    )
    (comp (ref "L6")
      (value "6.8uH")
      (footprint "eagle-import:IHL-2525CZ")
      (libsource (lib "eagle-import") (part "INDUCTORIHL2525CZ"))
    )
    (comp (ref "R10")
      (value "0.05 Ω")
      (footprint "eagle-import:0805_RES")
      (libsource (lib "eagle-import") (part "RESISTOR0805_RES"))
    )
    (comp (ref "R12")
      (value "1 kΩ")
      (footprint "eagle-import:0402_RES")
      (libsource (lib "eagle-import") (part "RESISTOR0402_RES"))
    )
    (comp (ref "R42")
      (value "23.2 kΩ")
      (footprint "eagle-import:0402_RES")
      (libsource (lib "eagle-import") (part "RESISTOR0402_RES"))
    )
    (comp (ref "R55")
      (value "301 kΩ")
      (footprint "eagle-import:0402_RES")
      (libsource (lib "eagle-import") (part "RESISTOR0402_RES"))
    )
    (comp (ref "R56")
      (value "340 kΩ")
      (footprint "eagle-import:0402_RES")
      (libsource (lib "eagle-import") (part "RESISTOR0402_RES"))
    )
    (comp (ref "R62")
      (value "953 kΩ")
      (footprint "eagle-import:0402_RES")
      (libsource (lib "eagle-import") (part "RESISTOR0402_RES"))
    )
    (comp (ref "U16")
      (value "LT3652")
      (footprint "eagle-import:DFN-12_3MM")
      (libsource (lib "eagle-import") (part "LT3652"))
    )
    (comp (ref "U17")
      (value "LM234")
      (footprint "eagle-import:SOIC-8")
      (libsource (lib "eagle-import") (part "LM234"))
    )
    (comp (ref "C14")
      (value "0.1 uF")
      (footprint "eagle-import:0402_CAP")
      (libsource (lib "eagle-import") (part "CAPACITOR0402_CAP"))
    )
    (comp (ref "C20")
      (value "0.1 uF")
      (footprint "eagle-import:0402_CAP")
      (libsource (lib "eagle-import") (part "CAPACITOR0402_CAP"))
    )
    (comp (ref "C21")
      (value "0.1 uF")
      (footprint "eagle-import:0402_CAP")
      (libsource (lib "eagle-import") (part "CAPACITOR0402_CAP"))
    )
    (comp (ref "C22")
      (value "0.1 uF")
      (footprint "eagle-import:0402_CAP")
      (libsource (lib "eagle-import") (part "CAPACITOR0402_CAP"))
    )
    (comp (ref "C24")
      (value "0.47 uF")
      (footprint "eagle-import:0402_CAP")
      (libsource (lib "eagle-import") (part "CAPACITOR0402_CAP"))
    )
    (comp (ref "C25")
      (value "0.47 uF")
      (footprint "eagle-import:0402_CAP")
      (libsource (lib "eagle-import") (part "CAPACITOR0402_CAP"))
    )
    (comp (ref "C26")
      (value "0.47 uF")
      (footprint "eagle-import:0402_CAP")
      (libsource (lib "eagle-import") (part "CAPACITOR0402_CAP"))
    )
    (comp (ref "C27")
      (value "0.82 uF")
      (footprint "eagle-import:0402_CAP")
      (libsource (lib "eagle-import") (part "CAPACITOR0402_CAP"))
    )
    (comp (ref "Q1")
      (value "MOSFET-NCHANNELFDD8580")
      (footprint "eagle-import:DPAK")
      (libsource (lib "eagle-import") (part "MOSFET-NCHANNELFDD8580"))
    )
    (comp (ref "R1")
      (value "0.010 Ω")
      (footprint "eagle-import:0805_RES")
      (libsource (lib "eagle-import") (part "RESISTOR0805_RES"))
    )
    (comp (ref "R11")
      (value "0.05 Ω")
      (footprint "eagle-import:0805_RES")
      (libsource (lib "eagle-import") (part "RESISTOR0805_RES"))
    )
    (comp (ref "R13")
      (value "1 kΩ")
      (footprint "eagle-import:0402_RES")
      (libsource (lib "eagle-import") (part "RESISTOR0402_RES"))
    )
    (comp (ref "R14")
      (value "1 MΩ")
      (footprint "eagle-import:0402_RES")
      (libsource (lib "eagle-import") (part "RESISTOR0402_RES"))
    )
    (comp (ref "R39")
      (value "2 kΩ")
      (footprint "eagle-import:0402_RES")
      (libsource (lib "eagle-import") (part "RESISTOR0402_RES"))
    )
    (comp (ref "R40")
      (value "2 kΩ")
      (footprint "eagle-import:0402_RES")
      (libsource (lib "eagle-import") (part "RESISTOR0402_RES"))
    )
    (comp (ref "R41")
      (value "2 kΩ")
      (footprint "eagle-import:0402_RES")
      (libsource (lib "eagle-import") (part "RESISTOR0402_RES"))
    )
    (comp (ref "R52")
      (value "150 Ω")
      (footprint "eagle-import:0402_RES")
      (libsource (lib "eagle-import") (part "RESISTOR0402_RES"))
    )
    (comp (ref "R53")
      (value "150 Ω")
      (footprint "eagle-import:0402_RES")
      (libsource (lib "eagle-import") (part "RESISTOR0402_RES"))
    )
    (comp (ref "S1")
      (value "TE_SSA12/SPDT")
      (footprint "eagle-import:TE_SSA12_SPDT")
      (libsource (lib "eagle-import") (part "TE_SSA12/SPDT"))
    )
    (comp (ref "U18")
      (value "MAX17205")
      (footprint "eagle-import:14-TDFN")
      (libsource (lib "eagle-import") (part "MAX17205"))
    )
    (comp (ref "U19")
      (value "ESDR0502N")
      (footprint "eagle-import:UDFN-6")
      (libsource (lib "eagle-import") (part "ESDR0502N"))
    )
    (comp (ref "U25")
      (value "PCA9544AQFN-N20")
      (footprint "eagle-import:QFN-N20")
      (libsource (lib "eagle-import") (part "PCA9544AQFN-N20"))
    )
    (comp (ref "U26")
      (value "LTC2943")
      (footprint "eagle-import:DFN-8")
      (libsource (lib "eagle-import") (part "LTC2943"))
    )
    (comp (ref "U27")
      (value "MAX6746")
      (footprint "eagle-import:SOT-23-8")
      (libsource (lib "eagle-import") (part "MAX6746"))
    )
    (comp (ref "U28")
      (value "3.3V")
      (footprint "eagle-import:SOT-23")
      (libsource (lib "eagle-import") (part "TILM34803.3V"))
    )
    (comp (ref "H1")
      (value "MOUNT-PAD-ROUND3.0")
      (footprint "eagle-import:3,0-PAD")
      (libsource (lib "eagle-import") (part "MOUNT-PAD-ROUND3.0"))
    )
    (comp (ref "H2")
      (value "MOUNT-PAD-ROUND3.0")
      (footprint "eagle-import:3,0-PAD")
      (libsource (lib "eagle-import") (part "MOUNT-PAD-ROUND3.0"))
    )
    (comp (ref "H3")
      (value "MOUNT-PAD-ROUND3.0")
      (footprint "eagle-import:3,0-PAD")
      (libsource (lib "eagle-import") (part "MOUNT-PAD-ROUND3.0"))
    )
    (comp (ref "H4")
      (value "MOUNT-PAD-ROUND3.0")
      (footprint "eagle-import:3,0-PAD")
      (libsource (lib "eagle-import") (part "MOUNT-PAD-ROUND3.0"))
    )
    (comp (ref "J1")
      (value "MODULE_POWER")
      (footprint "eagle-import:MODULE_POWER")
      (libsource (lib "eagle-import") (part "MODULE_POWER"))
    )
  )
  (nets
    (net (code "1") (name "GND") (class "Default")
      (node (ref "C1") (pin "2") (pinfunction "2_2") (pintype "bidirectional"))
      (node (ref "C10") (pin "2") (pinfunction "2_2") (pintype "bidirectional"))
      (node (ref "C11") (pin "2") (pinfunction "2_2") (pintype "bidirectional"))
      (node (ref "C12") (pin "2") (pinfunction "2_2") (pintype "bidirectional"))
      (node (ref "C13") (pin "2") (pinfunction "2_2") (pintype "bidirectional"))
      (node (ref "C15") (pin "2") (pinfunction "2_2") (pintype "bidirectional"))
      (node (ref "C16") (pin "2") (pinfunction "2_2") (pintype "bidirectional"))
      (node (ref "C17") (pin "2") (pinfunction "2_2") (pintype "bidirectional"))
      (node (ref "C18") (pin "2") (pinfunction "2_2") (pintype "bidirectional"))
      (node (ref "C19") (pin "2") (pinfunction "2_2") (pintype "bidirectional"))
      (node (ref "C2") (pin "2") (pinfunction "2_2") (pintype "bidirectional"))
      (node (ref "C20") (pin "2") (pinfunction "2_2") (pintype "bidirectional"))
      (node (ref "C23") (pin "2") (pinfunction "2_2") (pintype "bidirectional"))
      (node (ref "C29") (pin "1") (pinfunction "1_1") (pintype "bidirectional"))
      (node (ref "C3") (pin "2") (pinfunction "2_2") (pintype "bidirectional"))
      (node (ref "C30") (pin "1") (pinfunction "1_1") (pintype "bidirectional"))
      (node (ref "C31") (pin "1") (pinfunction "1_1") (pintype "bidirectional"))
      (node (ref "C32") (pin "1") (pinfunction "1_1") (pintype "bidirectional"))
      (node (ref "C33") (pin "1") (pinfunction "1_1") (pintype "bidirectional"))
      (node (ref "C34") (pin "P$2") (pinfunction "2_P$2") (pintype "bidirectional"))
      (node (ref "C35") (pin "P$2") (pinfunction "2_P$2") (pintype "bidirectional"))
      (node (ref "C36") (pin "P$2") (pinfunction "2_P$2") (pintype "bidirectional"))
      (node (ref "C37") (pin "P$2") (pinfunction "2_P$2") (pintype "bidirectional"))
      (node (ref "C38") (pin "P$2") (pinfunction "2_P$2") (pintype "bidirectional"))
      (node (ref "C39") (pin "P$2") (pinfunction "2_P$2") (pintype "bidirectional"))
      (node (ref "C4") (pin "2") (pinfunction "2_2") (pintype "bidirectional"))
      (node (ref "C40") (pin "P$2") (pinfunction "2_P$2") (pintype "bidirectional"))
      (node (ref "C41") (pin "1") (pinfunction "1_1") (pintype "bidirectional"))
      (node (ref "C42") (pin "1") (pinfunction "1_1") (pintype "bidirectional"))
      (node (ref "C43") (pin "1") (pinfunction "1_1") (pintype "bidirectional"))
      (node (ref "C44") (pin "1") (pinfunction "1_1") (pintype "bidirectional"))
      (node (ref "C45") (pin "1") (pinfunction "1_1") (pintype "bidirectional"))
      (node (ref "C46") (pin "1") (pinfunction "1_1") (pintype "bidirectional"))
      (node (ref "C47") (pin "1") (pinfunction "1_1") (pintype "bidirectional"))
      (node (ref "C48") (pin "1") (pinfunction "1_1") (pintype "bidirectional"))
      (node (ref "C49") (pin "1") (pinfunction "1_1") (pintype "bidirectional"))
      (node (ref "C5") (pin "2") (pinfunction "2_2") (pintype "bidirectional"))
      (node (ref "C50") (pin "1") (pinfunction "1_1") (pintype "bidirectional"))
      (node (ref "C6") (pin "2") (pinfunction "2_2") (pintype "bidirectional"))
      (node (ref "C7") (pin "2") (pinfunction "2_2") (pintype "bidirectional"))
      (node (ref "C8") (pin "2") (pinfunction "2_2") (pintype "bidirectional"))
      (node (ref "C9") (pin "2") (pinfunction "2_2") (pintype "bidirectional"))
      (node (ref "D1") (pin "P$1") (pinfunction "ANODE_P$1") (pintype "bidirectional"))
      (node (ref "H1") (pin "B3,0") (pinfunction "MOUNT_B3,0") (pintype "passive"))
      (node (ref "H2") (pin "B3,0") (pinfunction "MOUNT_B3,0") (pintype "passive"))
      (node (ref "H3") (pin "B3,0") (pinfunction "MOUNT_B3,0") (pintype "passive"))
      (node (ref "H4") (pin "B3,0") (pinfunction "MOUNT_B3,0") (pintype "passive"))
      (node (ref "J1") (pin "1") (pinfunction "GND_1") (pintype "power_in"))
      (node (ref "J1") (pin "20") (pinfunction "VSOL-_20") (pintype "power_in"))
      (node (ref "J3") (pin "3") (pinfunction "~{RESET}_3") (pintype "bidirectional"))
      (node (ref "JP1") (pin "1") (pinfunction "1_1") (pintype "passive"))
      (node (ref "Q1") (pin "4") (pinfunction "D_4") (pintype "passive"))
      (node (ref "R42") (pin "1") (pinfunction "1_1") (pintype "passive"))
      (node (ref "R48") (pin "1") (pinfunction "1_1") (pintype "passive"))
      (node (ref "R49") (pin "1") (pinfunction "1_1") (pintype "passive"))
      (node (ref "R50") (pin "1") (pinfunction "1_1") (pintype "passive"))
      (node (ref "R51") (pin "1") (pinfunction "1_1") (pintype "passive"))
      (node (ref "R54") (pin "1") (pinfunction "1_1") (pintype "passive"))
      (node (ref "R56") (pin "2") (pinfunction "2_2") (pintype "passive"))
      (node (ref "U1") (pin "15") (pinfunction "PGND_15") (pintype "bidirectional"))
      (node (ref "U1") (pin "16") (pinfunction "PGND_16") (pintype "bidirectional"))
      (node (ref "U1") (pin "6") (pinfunction "AGND_6") (pintype "bidirectional"))
      (node (ref "U1") (pin "7") (pinfunction "FSW_7") (pintype "bidirectional"))
      (node (ref "U1") (pin "8") (pinfunction "DEF_8") (pintype "bidirectional"))
      (node (ref "U1") (pin "GND") (pinfunction "PGND_GND") (pintype "bidirectional"))
      (node (ref "U10") (pin "P$1") (pinfunction "GND_P$1") (pintype "open_collector"))
      (node (ref "U10") (pin "P2") (pinfunction "GND_P2") (pintype "open_collector"))
      (node (ref "U10") (pin "P3") (pinfunction "GND_P3") (pintype "open_collector"))
      (node (ref "U10") (pin "P7") (pinfunction "GND_P7") (pintype "open_collector"))
      (node (ref "U11") (pin "P$1") (pinfunction "GND_P$1") (pintype "open_collector"))
      (node (ref "U11") (pin "P2") (pinfunction "GND_P2") (pintype "open_collector"))
      (node (ref "U11") (pin "P3") (pinfunction "GND_P3") (pintype "open_collector"))
      (node (ref "U11") (pin "P7") (pinfunction "GND_P7") (pintype "open_collector"))
      (node (ref "U12") (pin "P$1") (pinfunction "GND_P$1") (pintype "open_collector"))
      (node (ref "U12") (pin "P2") (pinfunction "GND_P2") (pintype "open_collector"))
      (node (ref "U12") (pin "P3") (pinfunction "GND_P3") (pintype "open_collector"))
      (node (ref "U12") (pin "P7") (pinfunction "GND_P7") (pintype "open_collector"))
      (node (ref "U13") (pin "P$1") (pinfunction "GND_P$1") (pintype "open_collector"))
      (node (ref "U13") (pin "P2") (pinfunction "GND_P2") (pintype "open_collector"))
      (node (ref "U13") (pin "P3") (pinfunction "GND_P3") (pintype "open_collector"))
      (node (ref "U13") (pin "P7") (pinfunction "GND_P7") (pintype "open_collector"))
      (node (ref "U14") (pin "P$1") (pinfunction "GND_P$1") (pintype "open_collector"))
      (node (ref "U14") (pin "P2") (pinfunction "GND_P2") (pintype "open_collector"))
      (node (ref "U14") (pin "P3") (pinfunction "GND_P3") (pintype "open_collector"))
      (node (ref "U14") (pin "P7") (pinfunction "GND_P7") (pintype "open_collector"))
      (node (ref "U15") (pin "P$1") (pinfunction "GND_P$1") (pintype "open_collector"))
      (node (ref "U15") (pin "P2") (pinfunction "GND_P2") (pintype "open_collector"))
      (node (ref "U15") (pin "P3") (pinfunction "GND_P3") (pintype "open_collector"))
      (node (ref "U15") (pin "P7") (pinfunction "GND_P7") (pintype "open_collector"))
      (node (ref "U16") (pin "13") (pinfunction "GND_13") (pintype "bidirectional"))
      (node (ref "U16") (pin "6") (pinfunction "TIMER_6") (pintype "bidirectional"))
      (node (ref "U2") (pin "15") (pinfunction "PGND_15") (pintype "bidirectional"))
      (node (ref "U2") (pin "16") (pinfunction "PGND_16") (pintype "bidirectional"))
      (node (ref "U2") (pin "6") (pinfunction "AGND_6") (pintype "bidirectional"))
      (node (ref "U2") (pin "7") (pinfunction "FSW_7") (pintype "bidirectional"))
      (node (ref "U2") (pin "8") (pinfunction "DEF_8") (pintype "bidirectional"))
      (node (ref "U2") (pin "GND") (pinfunction "PGND_GND") (pintype "bidirectional"))
      (node (ref "U20") (pin "2") (pinfunction "GND_2") (pintype "bidirectional"))
      (node (ref "U21") (pin "2") (pinfunction "GND_2") (pintype "bidirectional"))
      (node (ref "U22") (pin "2") (pinfunction "GND_2") (pintype "bidirectional"))
      (node (ref "U23") (pin "2") (pinfunction "GND_2") (pintype "bidirectional"))
      (node (ref "U24") (pin "2") (pinfunction "GND_2") (pintype "bidirectional"))
      (node (ref "U25") (pin "1") (pinfunction "A0_1") (pintype "bidirectional"))
      (node (ref "U25") (pin "10") (pinfunction "GND_10") (pintype "bidirectional"))
      (node (ref "U25") (pin "3") (pinfunction "A2_3") (pintype "bidirectional"))
      (node (ref "U26") (pin "P$1") (pinfunction "GND_P$1") (pintype "open_collector"))
      (node (ref "U26") (pin "P2") (pinfunction "GND_P2") (pintype "open_collector"))
      (node (ref "U26") (pin "P3") (pinfunction "GND_P3") (pintype "open_collector"))
      (node (ref "U26") (pin "P7") (pinfunction "GND_P7") (pintype "open_collector"))
      (node (ref "U29") (pin "1") (pinfunction "E0_1") (pintype "bidirectional"))
      (node (ref "U29") (pin "2") (pinfunction "E1_2") (pintype "bidirectional"))
      (node (ref "U29") (pin "3") (pinfunction "E2_3") (pintype "bidirectional"))
      (node (ref "U29") (pin "4") (pinfunction "GND_4") (pintype "bidirectional"))
      (node (ref "U3") (pin "15") (pinfunction "PGND_15") (pintype "bidirectional"))
      (node (ref "U3") (pin "16") (pinfunction "PGND_16") (pintype "bidirectional"))
      (node (ref "U3") (pin "6") (pinfunction "AGND_6") (pintype "bidirectional"))
      (node (ref "U3") (pin "7") (pinfunction "FSW_7") (pintype "bidirectional"))
      (node (ref "U3") (pin "8") (pinfunction "DEF_8") (pintype "bidirectional"))
      (node (ref "U3") (pin "GND") (pinfunction "PGND_GND") (pintype "bidirectional"))
      (node (ref "U4") (pin "15") (pinfunction "PGND_15") (pintype "bidirectional"))
      (node (ref "U4") (pin "16") (pinfunction "PGND_16") (pintype "bidirectional"))
      (node (ref "U4") (pin "6") (pinfunction "AGND_6") (pintype "bidirectional"))
      (node (ref "U4") (pin "7") (pinfunction "FSW_7") (pintype "bidirectional"))
      (node (ref "U4") (pin "8") (pinfunction "DEF_8") (pintype "bidirectional"))
      (node (ref "U4") (pin "GND") (pinfunction "PGND_GND") (pintype "bidirectional"))
      (node (ref "U5") (pin "15") (pinfunction "PGND_15") (pintype "bidirectional"))
      (node (ref "U5") (pin "16") (pinfunction "PGND_16") (pintype "bidirectional"))
      (node (ref "U5") (pin "6") (pinfunction "AGND_6") (pintype "bidirectional"))
      (node (ref "U5") (pin "7") (pinfunction "FSW_7") (pintype "bidirectional"))
      (node (ref "U5") (pin "8") (pinfunction "DEF_8") (pintype "bidirectional"))
      (node (ref "U5") (pin "GND") (pinfunction "PGND_GND") (pintype "bidirectional"))
      (node (ref "U6") (pin "1") (pinfunction "A0_1") (pintype "bidirectional"))
      (node (ref "U6") (pin "10") (pinfunction "GND_10") (pintype "bidirectional"))
      (node (ref "U6") (pin "2") (pinfunction "A1_2") (pintype "bidirectional"))
      (node (ref "U6") (pin "3") (pinfunction "A2_3") (pintype "bidirectional"))
      (node (ref "U7") (pin "10") (pinfunction "GND_10") (pintype "bidirectional"))
      (node (ref "U7") (pin "2") (pinfunction "A1_2") (pintype "bidirectional"))
      (node (ref "U7") (pin "3") (pinfunction "A2_3") (pintype "bidirectional"))
      (node (ref "U8") (pin "P$1") (pinfunction "GND_P$1") (pintype "open_collector"))
      (node (ref "U8") (pin "P2") (pinfunction "GND_P2") (pintype "open_collector"))
      (node (ref "U8") (pin "P3") (pinfunction "GND_P3") (pintype "open_collector"))
      (node (ref "U8") (pin "P7") (pinfunction "GND_P7") (pintype "open_collector"))
      (node (ref "U9") (pin "P$1") (pinfunction "GND_P$1") (pintype "open_collector"))
      (node (ref "U9") (pin "P2") (pinfunction "GND_P2") (pintype "open_collector"))
      (node (ref "U9") (pin "P3") (pinfunction "GND_P3") (pintype "open_collector"))
      (node (ref "U9") (pin "P7") (pinfunction "GND_P7") (pintype "open_collector"))
    )
    (net (code "2") (name "Net-(D1-CATHODE)") (class "Default")
      (node (ref "C28") (pin "1") (pinfunction "1_1") (pintype "bidirectional"))
      (node (ref "D1") (pin "P$3") (pinfunction "CATHODE_P$3") (pintype "bidirectional"))
      (node (ref "L6") (pin "P$1") (pinfunction "1_P$1") (pintype "bidirectional"))
      (node (ref "U16") (pin "12") (pinfunction "SW_12") (pintype "bidirectional"))
    )
    (net (code "3") (name "Net-(D2-ANODE)") (class "Default")
      (node (ref "D2") (pin "P$2") (pinfunction "ANODE_P$2") (pintype "bidirectional"))
      (node (ref "D3") (pin "P$1") (pinfunction "ANODE_P$1") (pintype "bidirectional"))
    )
    (net (code "4") (name "Net-(D3-CATHODE)") (class "Default")
      (node (ref "C28") (pin "2") (pinfunction "2_2") (pintype "bidirectional"))
      (node (ref "D3") (pin "P$3") (pinfunction "CATHODE_P$3") (pintype "bidirectional"))
      (node (ref "U16") (pin "11") (pinfunction "BOOST_11") (pintype "bidirectional"))
    )
    (net (code "5") (name "Net-(L1-1)") (class "Default")
      (node (ref "L1") (pin "P$1") (pinfunction "1_P$1") (pintype "bidirectional"))
      (node (ref "U1") (pin "1") (pinfunction "SW_1") (pintype "bidirectional"))
      (node (ref "U1") (pin "2") (pinfunction "SW_2") (pintype "bidirectional"))
      (node (ref "U1") (pin "3") (pinfunction "SW_3") (pintype "bidirectional"))
    )
    (net (code "6") (name "Net-(L1-2)") (class "Default")
      (node (ref "C42") (pin "2") (pinfunction "2_2") (pintype "bidirectional"))
      (node (ref "L1") (pin "P$2") (pinfunction "2_P$2") (pintype "bidirectional"))
      (node (ref "R44") (pin "2") (pinfunction "2_2") (pintype "passive"))
      (node (ref "R57") (pin "2") (pinfunction "2_2") (pintype "passive"))
      (node (ref "U1") (pin "14") (pinfunction "VOS_14") (pintype "bidirectional"))
      (node (ref "U21") (pin "1") (pinfunction "IN_1") (pintype "bidirectional"))
      (node (ref "U21") (pin "3") (pinfunction "EN_3") (pintype "bidirectional"))
    )
    (net (code "7") (name "Net-(L2-1)") (class "Default")
      (node (ref "L2") (pin "P$1") (pinfunction "1_P$1") (pintype "bidirectional"))
      (node (ref "U2") (pin "1") (pinfunction "SW_1") (pintype "bidirectional"))
      (node (ref "U2") (pin "2") (pinfunction "SW_2") (pintype "bidirectional"))
      (node (ref "U2") (pin "3") (pinfunction "SW_3") (pintype "bidirectional"))
    )
    (net (code "8") (name "Net-(L2-2)") (class "Default")
      (node (ref "C43") (pin "2") (pinfunction "2_2") (pintype "bidirectional"))
      (node (ref "L2") (pin "P$2") (pinfunction "2_P$2") (pintype "bidirectional"))
      (node (ref "R45") (pin "2") (pinfunction "2_2") (pintype "passive"))
      (node (ref "R58") (pin "2") (pinfunction "2_2") (pintype "passive"))
      (node (ref "U2") (pin "14") (pinfunction "VOS_14") (pintype "bidirectional"))
      (node (ref "U22") (pin "1") (pinfunction "IN_1") (pintype "bidirectional"))
      (node (ref "U22") (pin "3") (pinfunction "EN_3") (pintype "bidirectional"))
    )
    (net (code "9") (name "Net-(L3-1)") (class "Default")
      (node (ref "L3") (pin "P$1") (pinfunction "1_P$1") (pintype "bidirectional"))
      (node (ref "U3") (pin "1") (pinfunction "SW_1") (pintype "bidirectional"))
      (node (ref "U3") (pin "2") (pinfunction "SW_2") (pintype "bidirectional"))
      (node (ref "U3") (pin "3") (pinfunction "SW_3") (pintype "bidirectional"))
    )
    (net (code "10") (name "Net-(L3-2)") (class "Default")
      (node (ref "C44") (pin "2") (pinfunction "2_2") (pintype "bidirectional"))
      (node (ref "L3") (pin "P$2") (pinfunction "2_P$2") (pintype "bidirectional"))
      (node (ref "R46") (pin "2") (pinfunction "2_2") (pintype "passive"))
      (node (ref "R59") (pin "2") (pinfunction "2_2") (pintype "passive"))
      (node (ref "U23") (pin "1") (pinfunction "IN_1") (pintype "bidirectional"))
      (node (ref "U23") (pin "3") (pinfunction "EN_3") (pintype "bidirectional"))
      (node (ref "U3") (pin "14") (pinfunction "VOS_14") (pintype "bidirectional"))
    )
    (net (code "11") (name "Net-(L4-1)") (class "Default")
      (node (ref "L4") (pin "P$1") (pinfunction "1_P$1") (pintype "bidirectional"))
      (node (ref "U4") (pin "1") (pinfunction "SW_1") (pintype "bidirectional"))
      (node (ref "U4") (pin "2") (pinfunction "SW_2") (pintype "bidirectional"))
      (node (ref "U4") (pin "3") (pinfunction "SW_3") (pintype "bidirectional"))
    )
    (net (code "12") (name "Net-(L4-2)") (class "Default")
      (node (ref "C41") (pin "2") (pinfunction "2_2") (pintype "bidirectional"))
      (node (ref "L4") (pin "P$2") (pinfunction "2_P$2") (pintype "bidirectional"))
      (node (ref "R43") (pin "2") (pinfunction "2_2") (pintype "passive"))
      (node (ref "R61") (pin "2") (pinfunction "2_2") (pintype "passive"))
      (node (ref "U20") (pin "1") (pinfunction "IN_1") (pintype "bidirectional"))
      (node (ref "U20") (pin "3") (pinfunction "EN_3") (pintype "bidirectional"))
      (node (ref "U4") (pin "14") (pinfunction "VOS_14") (pintype "bidirectional"))
    )
    (net (code "13") (name "Net-(L5-1)") (class "Default")
      (node (ref "L5") (pin "P$1") (pinfunction "1_P$1") (pintype "bidirectional"))
      (node (ref "U5") (pin "1") (pinfunction "SW_1") (pintype "bidirectional"))
      (node (ref "U5") (pin "2") (pinfunction "SW_2") (pintype "bidirectional"))
      (node (ref "U5") (pin "3") (pinfunction "SW_3") (pintype "bidirectional"))
    )
    (net (code "14") (name "Net-(L5-2)") (class "Default")
      (node (ref "C45") (pin "2") (pinfunction "2_2") (pintype "bidirectional"))
      (node (ref "L5") (pin "P$2") (pinfunction "2_P$2") (pintype "bidirectional"))
      (node (ref "R47") (pin "2") (pinfunction "2_2") (pintype "passive"))
      (node (ref "R60") (pin "2") (pinfunction "2_2") (pintype "passive"))
      (node (ref "U24") (pin "1") (pinfunction "IN_1") (pintype "bidirectional"))
      (node (ref "U24") (pin "3") (pinfunction "EN_3") (pintype "bidirectional"))
      (node (ref "U5") (pin "14") (pinfunction "VOS_14") (pintype "bidirectional"))
    )
    (net (code "15") (name "Net-(L6-2)") (class "Default")
      (node (ref "L6") (pin "P$2") (pinfunction "2_P$2") (pintype "bidirectional"))
      (node (ref "R10") (pin "1") (pinfunction "1_1") (pintype "passive"))
      (node (ref "U16") (pin "10") (pinfunction "SENSE_10") (pintype "bidirectional"))
    )
    (net (code "16") (name "Net-(Q1-G)") (class "Default")
      (node (ref "Q1") (pin "1") (pinfunction "G_1") (pintype "passive"))
      (node (ref "R14") (pin "2") (pinfunction "2_2") (pintype "passive"))
      (node (ref "U27") (pin "7") (pinfunction "~{RESET}_7") (pintype "bidirectional"))
    )
    (net (code "17") (name "Net-(S1-B)") (class "Default")
      (node (ref "C26") (pin "1") (pinfunction "1_1") (pintype "bidirectional"))
      (node (ref "S1") (pin "2") (pinfunction "B_2") (pintype "bidirectional"))
    )
    (net (code "18") (name "Net-(U1-FB)") (class "Default")
      (node (ref "R48") (pin "2") (pinfunction "2_2") (pintype "passive"))
      (node (ref "R57") (pin "1") (pinfunction "1_1") (pintype "passive"))
      (node (ref "U1") (pin "5") (pinfunction "FB_5") (pintype "bidirectional"))
    )
    (net (code "19") (name "Net-(U1-PG)") (class "Default")
      (node (ref "R44") (pin "1") (pinfunction "1_1") (pintype "passive"))
      (node (ref "U1") (pin "4") (pinfunction "PG_4") (pintype "bidirectional"))
    )
    (net (code "20") (name "Net-(U1-SS{slash}TR)") (class "Default")
      (node (ref "C30") (pin "2") (pinfunction "2_2") (pintype "bidirectional"))
      (node (ref "U1") (pin "9") (pinfunction "SS/TR_9") (pintype "bidirectional"))
    )
    (net (code "21") (name "Net-(U2-FB)") (class "Default")
      (node (ref "R49") (pin "2") (pinfunction "2_2") (pintype "passive"))
      (node (ref "R58") (pin "1") (pinfunction "1_1") (pintype "passive"))
      (node (ref "U2") (pin "5") (pinfunction "FB_5") (pintype "bidirectional"))
    )
    (net (code "22") (name "Net-(U2-PG)") (class "Default")
      (node (ref "R45") (pin "1") (pinfunction "1_1") (pintype "passive"))
      (node (ref "U2") (pin "4") (pinfunction "PG_4") (pintype "bidirectional"))
    )
    (net (code "23") (name "Net-(U2-SS{slash}TR)") (class "Default")
      (node (ref "C31") (pin "2") (pinfunction "2_2") (pintype "bidirectional"))
      (node (ref "U2") (pin "9") (pinfunction "SS/TR_9") (pintype "bidirectional"))
    )
    (net (code "24") (name "Net-(U3-FB)") (class "Default")
      (node (ref "R50") (pin "2") (pinfunction "2_2") (pintype "passive"))
      (node (ref "R59") (pin "1") (pinfunction "1_1") (pintype "passive"))
      (node (ref "U3") (pin "5") (pinfunction "FB_5") (pintype "bidirectional"))
    )
    (net (code "25") (name "Net-(U3-PG)") (class "Default")
      (node (ref "R46") (pin "1") (pinfunction "1_1") (pintype "passive"))
      (node (ref "U3") (pin "4") (pinfunction "PG_4") (pintype "bidirectional"))
    )
    (net (code "26") (name "Net-(U3-SS{slash}TR)") (class "Default")
      (node (ref "C32") (pin "2") (pinfunction "2_2") (pintype "bidirectional"))
      (node (ref "U3") (pin "9") (pinfunction "SS/TR_9") (pintype "bidirectional"))
    )
    (net (code "27") (name "Net-(U4-FB)") (class "Default")
      (node (ref "R54") (pin "2") (pinfunction "2_2") (pintype "passive"))
      (node (ref "R61") (pin "1") (pinfunction "1_1") (pintype "passive"))
      (node (ref "U4") (pin "5") (pinfunction "FB_5") (pintype "bidirectional"))
    )
    (net (code "28") (name "Net-(U4-PG)") (class "Default")
      (node (ref "R43") (pin "1") (pinfunction "1_1") (pintype "passive"))
      (node (ref "U4") (pin "4") (pinfunction "PG_4") (pintype "bidirectional"))
    )
    (net (code "29") (name "Net-(U4-SS{slash}TR)") (class "Default")
      (node (ref "C29") (pin "2") (pinfunction "2_2") (pintype "bidirectional"))
      (node (ref "U4") (pin "9") (pinfunction "SS/TR_9") (pintype "bidirectional"))
    )
    (net (code "30") (name "Net-(U5-FB)") (class "Default")
      (node (ref "R51") (pin "2") (pinfunction "2_2") (pintype "passive"))
      (node (ref "R60") (pin "1") (pinfunction "1_1") (pintype "passive"))
      (node (ref "U5") (pin "5") (pinfunction "FB_5") (pintype "bidirectional"))
    )
    (net (code "31") (name "Net-(U5-PG)") (class "Default")
      (node (ref "R47") (pin "1") (pinfunction "1_1") (pintype "passive"))
      (node (ref "U5") (pin "4") (pinfunction "PG_4") (pintype "bidirectional"))
    )
    (net (code "32") (name "Net-(U5-SS{slash}TR)") (class "Default")
      (node (ref "C33") (pin "2") (pinfunction "2_2") (pintype "bidirectional"))
      (node (ref "U5") (pin "9") (pinfunction "SS/TR_9") (pintype "bidirectional"))
    )
    (net (code "33") (name "Net-(U6-SC0)") (class "Default")
      (node (ref "R16") (pin "1") (pinfunction "1_1") (pintype "passive"))
      (node (ref "U6") (pin "6") (pinfunction "SC0_6") (pintype "bidirectional"))
      (node (ref "U8") (pin "P4") (pinfunction "SCL_P4") (pintype "open_collector"))
    )
    (net (code "34") (name "Net-(U6-SC1)") (class "Default")
      (node (ref "R19") (pin "1") (pinfunction "1_1") (pintype "passive"))
      (node (ref "U6") (pin "9") (pinfunction "SC1_9") (pintype "bidirectional"))
      (node (ref "U9") (pin "P4") (pinfunction "SCL_P4") (pintype "open_collector"))
    )
    (net (code "35") (name "Net-(U6-SD0)") (class "Default")
      (node (ref "R15") (pin "1") (pinfunction "1_1") (pintype "passive"))
      (node (ref "U6") (pin "5") (pinfunction "SD0_5") (pintype "bidirectional"))
      (node (ref "U8") (pin "P5") (pinfunction "SDA_P5") (pintype "open_collector"))
    )
    (net (code "36") (name "Net-(U6-SD1)") (class "Default")
      (node (ref "R18") (pin "1") (pinfunction "1_1") (pintype "passive"))
      (node (ref "U6") (pin "8") (pinfunction "SD1_8") (pintype "bidirectional"))
      (node (ref "U9") (pin "P5") (pinfunction "SDA_P5") (pintype "open_collector"))
    )
    (net (code "37") (name "Net-(U6-~{INT0})") (class "Default")
      (node (ref "R17") (pin "1") (pinfunction "1_1") (pintype "passive"))
      (node (ref "U6") (pin "4") (pinfunction "~{INT0}_4") (pintype "bidirectional"))
      (node (ref "U8") (pin "P6") (pinfunction "~{ALERT}_P6") (pintype "open_collector"))
    )
    (net (code "38") (name "Net-(U6-~{INT1})") (class "Default")
      (node (ref "R20") (pin "1") (pinfunction "1_1") (pintype "passive"))
      (node (ref "U6") (pin "7") (pinfunction "~{INT1}_7") (pintype "bidirectional"))
      (node (ref "U9") (pin "P6") (pinfunction "~{ALERT}_P6") (pintype "open_collector"))
    )
    (net (code "39") (name "Net-(U10-SCL)") (class "Default")
      (node (ref "R22") (pin "1") (pinfunction "1_1") (pintype "passive"))
      (node (ref "U10") (pin "P4") (pinfunction "SCL_P4") (pintype "open_collector"))
      (node (ref "U6") (pin "13") (pinfunction "SC2_13") (pintype "bidirectional"))
    )
    (net (code "40") (name "Net-(U10-SDA)") (class "Default")
      (node (ref "R21") (pin "1") (pinfunction "1_1") (pintype "passive"))
      (node (ref "U10") (pin "P5") (pinfunction "SDA_P5") (pintype "open_collector"))
      (node (ref "U6") (pin "12") (pinfunction "SD2_12") (pintype "bidirectional"))
    )
    (net (code "41") (name "Net-(U10-~{ALERT})") (class "Default")
      (node (ref "R23") (pin "1") (pinfunction "1_1") (pintype "passive"))
      (node (ref "U10") (pin "P6") (pinfunction "~{ALERT}_P6") (pintype "open_collector"))
      (node (ref "U6") (pin "11") (pinfunction "~{INT2}_11") (pintype "bidirectional"))
    )
    (net (code "42") (name "Net-(U11-SCL)") (class "Default")
      (node (ref "R25") (pin "1") (pinfunction "1_1") (pintype "passive"))
      (node (ref "U11") (pin "P4") (pinfunction "SCL_P4") (pintype "open_collector"))
      (node (ref "U6") (pin "16") (pinfunction "SC3_16") (pintype "bidirectional"))
    )
    (net (code "43") (name "Net-(U11-SDA)") (class "Default")
      (node (ref "R24") (pin "1") (pinfunction "1_1") (pintype "passive"))
      (node (ref "U11") (pin "P5") (pinfunction "SDA_P5") (pintype "open_collector"))
      (node (ref "U6") (pin "15") (pinfunction "SD3_15") (pintype "bidirectional"))
    )
    (net (code "44") (name "Net-(U11-~{ALERT})") (class "Default")
      (node (ref "R26") (pin "1") (pinfunction "1_1") (pintype "passive"))
      (node (ref "U11") (pin "P6") (pinfunction "~{ALERT}_P6") (pintype "open_collector"))
      (node (ref "U6") (pin "14") (pinfunction "~{INT3}_14") (pintype "bidirectional"))
    )
    (net (code "45") (name "Net-(U12-SCL)") (class "Default")
      (node (ref "R34") (pin "1") (pinfunction "1_1") (pintype "passive"))
      (node (ref "U12") (pin "P4") (pinfunction "SCL_P4") (pintype "open_collector"))
      (node (ref "U7") (pin "6") (pinfunction "SC0_6") (pintype "bidirectional"))
    )
    (net (code "46") (name "Net-(U12-SDA)") (class "Default")
      (node (ref "R33") (pin "1") (pinfunction "1_1") (pintype "passive"))
      (node (ref "U12") (pin "P5") (pinfunction "SDA_P5") (pintype "open_collector"))
      (node (ref "U7") (pin "5") (pinfunction "SD0_5") (pintype "bidirectional"))
    )
    (net (code "47") (name "Net-(U12-~{ALERT})") (class "Default")
      (node (ref "R35") (pin "1") (pinfunction "1_1") (pintype "passive"))
      (node (ref "U12") (pin "P6") (pinfunction "~{ALERT}_P6") (pintype "open_collector"))
      (node (ref "U7") (pin "4") (pinfunction "~{INT0}_4") (pintype "bidirectional"))
    )
    (net (code "48") (name "Net-(U13-SCL)") (class "Default")
      (node (ref "R31") (pin "1") (pinfunction "1_1") (pintype "passive"))
      (node (ref "U13") (pin "P4") (pinfunction "SCL_P4") (pintype "open_collector"))
      (node (ref "U7") (pin "9") (pinfunction "SC1_9") (pintype "bidirectional"))
    )
    (net (code "49") (name "Net-(U13-SDA)") (class "Default")
      (node (ref "R30") (pin "1") (pinfunction "1_1") (pintype "passive"))
      (node (ref "U13") (pin "P5") (pinfunction "SDA_P5") (pintype "open_collector"))
      (node (ref "U7") (pin "8") (pinfunction "SD1_8") (pintype "bidirectional"))
    )
    (net (code "50") (name "Net-(U13-~{ALERT})") (class "Default")
      (node (ref "R32") (pin "1") (pinfunction "1_1") (pintype "passive"))
      (node (ref "U13") (pin "P6") (pinfunction "~{ALERT}_P6") (pintype "open_collector"))
      (node (ref "U7") (pin "7") (pinfunction "~{INT1}_7") (pintype "bidirectional"))
    )
    (net (code "51") (name "Net-(U14-SCL)") (class "Default")
      (node (ref "R28") (pin "1") (pinfunction "1_1") (pintype "passive"))
      (node (ref "U14") (pin "P4") (pinfunction "SCL_P4") (pintype "open_collector"))
      (node (ref "U7") (pin "13") (pinfunction "SC2_13") (pintype "bidirectional"))
    )
    (net (code "52") (name "Net-(U14-SDA)") (class "Default")
      (node (ref "R27") (pin "1") (pinfunction "1_1") (pintype "passive"))
      (node (ref "U14") (pin "P5") (pinfunction "SDA_P5") (pintype "open_collector"))
      (node (ref "U7") (pin "12") (pinfunction "SD2_12") (pintype "bidirectional"))
    )
    (net (code "53") (name "Net-(U14-~{ALERT})") (class "Default")
      (node (ref "R29") (pin "1") (pinfunction "1_1") (pintype "passive"))
      (node (ref "U14") (pin "P6") (pinfunction "~{ALERT}_P6") (pintype "open_collector"))
      (node (ref "U7") (pin "11") (pinfunction "~{INT2}_11") (pintype "bidirectional"))
    )
    (net (code "54") (name "Net-(U15-SCL)") (class "Default")
      (node (ref "R37") (pin "1") (pinfunction "1_1") (pintype "passive"))
      (node (ref "U15") (pin "P4") (pinfunction "SCL_P4") (pintype "open_collector"))
      (node (ref "U7") (pin "16") (pinfunction "SC3_16") (pintype "bidirectional"))
    )
    (net (code "55") (name "Net-(U15-SDA)") (class "Default")
      (node (ref "R36") (pin "1") (pinfunction "1_1") (pintype "passive"))
      (node (ref "U15") (pin "P5") (pinfunction "SDA_P5") (pintype "open_collector"))
      (node (ref "U7") (pin "15") (pinfunction "SD3_15") (pintype "bidirectional"))
    )
    (net (code "56") (name "Net-(U15-~{ALERT})") (class "Default")
      (node (ref "R38") (pin "1") (pinfunction "1_1") (pintype "passive"))
      (node (ref "U15") (pin "P6") (pinfunction "~{ALERT}_P6") (pintype "open_collector"))
      (node (ref "U7") (pin "14") (pinfunction "~{INT3}_14") (pintype "bidirectional"))
    )
    (net (code "57") (name "Net-(U16-VFB)") (class "Default")
      (node (ref "R56") (pin "1") (pinfunction "1_1") (pintype "passive"))
      (node (ref "R62") (pin "1") (pinfunction "1_1") (pintype "passive"))
      (node (ref "U16") (pin "7") (pinfunction "VFB_7") (pintype "bidirectional"))
    )
    (net (code "58") (name "Net-(U16-VIN_REG)") (class "Default")
      (node (ref "R12") (pin "1") (pinfunction "1_1") (pintype "passive"))
      (node (ref "R42") (pin "2") (pinfunction "2_2") (pintype "passive"))
      (node (ref "R55") (pin "1") (pinfunction "1_1") (pintype "passive"))
      (node (ref "U16") (pin "2") (pinfunction "VIN_REG_2") (pintype "bidirectional"))
      (node (ref "U17") (pin "6") (pinfunction "V-_6") (pintype "bidirectional"))
    )
    (net (code "59") (name "Net-(U17-R)") (class "Default")
      (node (ref "R12") (pin "2") (pinfunction "2_2") (pintype "passive"))
      (node (ref "U17") (pin "1") (pinfunction "R_1") (pintype "bidirectional"))
    )
    (net (code "60") (name "Net-(U18-ALRT1)") (class "Default")
      (node (ref "R53") (pin "1") (pinfunction "1_1") (pintype "passive"))
      (node (ref "U18") (pin "8") (pinfunction "ALRT1_8") (pintype "bidirectional"))
      (node (ref "U19") (pin "P$6") (pinfunction "VUSB_P$6") (pintype "bidirectional"))
    )
    (net (code "61") (name "Net-(U18-REG2)") (class "Default")
      (node (ref "C24") (pin "1") (pinfunction "1_1") (pintype "bidirectional"))
      (node (ref "U18") (pin "3") (pinfunction "REG2_3") (pintype "bidirectional"))
    )
    (net (code "62") (name "Net-(U18-REG3)") (class "Default")
      (node (ref "C25") (pin "1") (pinfunction "1_1") (pintype "bidirectional"))
      (node (ref "U18") (pin "1") (pinfunction "REG3_1") (pintype "bidirectional"))
    )
    (net (code "63") (name "Net-(U18-SCL)") (class "Default")
      (node (ref "R52") (pin "1") (pinfunction "1_1") (pintype "passive"))
      (node (ref "U18") (pin "11") (pinfunction "SCL_11") (pintype "bidirectional"))
      (node (ref "U19") (pin "P$5") (pinfunction "D+_P$5") (pintype "bidirectional"))
    )
    (net (code "64") (name "Net-(U18-SDA)") (class "Default")
      (node (ref "R13") (pin "1") (pinfunction "1_1") (pintype "passive"))
      (node (ref "U18") (pin "12") (pinfunction "SDA_12") (pintype "bidirectional"))
      (node (ref "U19") (pin "P$4") (pinfunction "D-_P$4") (pintype "bidirectional"))
    )
    (net (code "65") (name "Net-(U25-SC0)") (class "Default")
      (node (ref "R40") (pin "1") (pinfunction "1_1") (pintype "passive"))
      (node (ref "U25") (pin "6") (pinfunction "SC0_6") (pintype "bidirectional"))
      (node (ref "U26") (pin "P4") (pinfunction "SCL_P4") (pintype "open_collector"))
    )
    (net (code "66") (name "Net-(U25-SD0)") (class "Default")
      (node (ref "R39") (pin "1") (pinfunction "1_1") (pintype "passive"))
      (node (ref "U25") (pin "5") (pinfunction "SD0_5") (pintype "bidirectional"))
      (node (ref "U26") (pin "P5") (pinfunction "SDA_P5") (pintype "open_collector"))
    )
    (net (code "67") (name "Net-(U25-~{INT0})") (class "Default")
      (node (ref "R41") (pin "1") (pinfunction "1_1") (pintype "passive"))
      (node (ref "U25") (pin "4") (pinfunction "~{INT0}_4") (pintype "bidirectional"))
      (node (ref "U26") (pin "P6") (pinfunction "~{ALERT}_P6") (pintype "open_collector"))
    )
    (net (code "68") (name "Net-(U27-SRT)") (class "Default")
      (node (ref "C27") (pin "1") (pinfunction "1_1") (pintype "bidirectional"))
      (node (ref "U27") (pin "3") (pinfunction "SRT_3") (pintype "bidirectional"))
    )
    (net (code "69") (name "Net-(U27-SWT)") (class "Default")
      (node (ref "S1") (pin "IN") (pinfunction "IN_IN") (pintype "bidirectional"))
      (node (ref "U27") (pin "2") (pinfunction "SWT_2") (pintype "bidirectional"))
    )
    (net (code "70") (name "Net-(U27-VCC)") (class "Default")
      (node (ref "C22") (pin "1") (pinfunction "1_1") (pintype "bidirectional"))
      (node (ref "U27") (pin "1") (pinfunction "~{MR}_1") (pintype "bidirectional"))
      (node (ref "U27") (pin "5") (pinfunction "WDS_5") (pintype "bidirectional"))
      (node (ref "U27") (pin "8") (pinfunction "VCC_8") (pintype "bidirectional"))
      (node (ref "U28") (pin "1") (pinfunction "OUT_1") (pintype "bidirectional"))
    )
    (net (code "71") (name "Net-(U29-~{WC})") (class "Default")
      (node (ref "SJ1") (pin "2") (pinfunction "2_2") (pintype "passive"))
      (node (ref "U29") (pin "7") (pinfunction "~{WC}_7") (pintype "bidirectional"))
    )
    (net (code "72") (name "SCL") (class "Default")
      (node (ref "J1") (pin "5") (pinfunction "SMBCLK_5") (pintype "open_collector"))
      (node (ref "J3") (pin "1") (pinfunction "VCC_1") (pintype "bidirectional"))
      (node (ref "R52") (pin "2") (pinfunction "2_2") (pintype "passive"))
      (node (ref "U25") (pin "18") (pinfunction "SCL_18") (pintype "bidirectional"))
      (node (ref "U29") (pin "6") (pinfunction "SCL_6") (pintype "bidirectional"))
      (node (ref "U6") (pin "18") (pinfunction "SCL_18") (pintype "bidirectional"))
      (node (ref "U7") (pin "18") (pinfunction "SCL_18") (pintype "bidirectional"))
    )
    (net (code "73") (name "SDA") (class "Default")
      (node (ref "J1") (pin "3") (pinfunction "SMBDATA_3") (pintype "open_collector"))
      (node (ref "J3") (pin "5") (pinfunction "GND_5") (pintype "bidirectional"))
      (node (ref "R13") (pin "2") (pinfunction "2_2") (pintype "passive"))
      (node (ref "U25") (pin "19") (pinfunction "SDA_19") (pintype "bidirectional"))
      (node (ref "U29") (pin "5") (pinfunction "SDA_5") (pintype "bidirectional"))
      (node (ref "U6") (pin "19") (pinfunction "SDA_19") (pintype "bidirectional"))
      (node (ref "U7") (pin "19") (pinfunction "SDA_19") (pintype "bidirectional"))
    )
    (net (code "74") (name "VBAT+") (class "Default")
      (node (ref "C10") (pin "1") (pinfunction "1_1") (pintype "bidirectional"))
      (node (ref "C11") (pin "1") (pinfunction "1_1") (pintype "bidirectional"))
      (node (ref "C12") (pin "1") (pinfunction "1_1") (pintype "bidirectional"))
      (node (ref "C13") (pin "1") (pinfunction "1_1") (pintype "bidirectional"))
      (node (ref "C14") (pin "1") (pinfunction "1_1") (pintype "bidirectional"))
      (node (ref "C21") (pin "1") (pinfunction "1_1") (pintype "bidirectional"))
      (node (ref "C34") (pin "P$1") (pinfunction "1_P$1") (pintype "bidirectional"))
      (node (ref "C35") (pin "P$1") (pinfunction "1_P$1") (pintype "bidirectional"))
      (node (ref "C36") (pin "P$1") (pinfunction "1_P$1") (pintype "bidirectional"))
      (node (ref "C37") (pin "P$1") (pinfunction "1_P$1") (pintype "bidirectional"))
      (node (ref "C38") (pin "P$1") (pinfunction "1_P$1") (pintype "bidirectional"))
      (node (ref "C39") (pin "P$1") (pinfunction "1_P$1") (pintype "bidirectional"))
      (node (ref "C9") (pin "1") (pinfunction "1_1") (pintype "bidirectional"))
      (node (ref "D2") (pin "P$1") (pinfunction "CATHODE_P$1") (pintype "bidirectional"))
      (node (ref "J1") (pin "17") (pinfunction "VBATT+_17") (pintype "power_in"))
      (node (ref "JP1") (pin "4") (pinfunction "4_4") (pintype "passive"))
      (node (ref "R10") (pin "2") (pinfunction "2_2") (pintype "passive"))
      (node (ref "R62") (pin "2") (pinfunction "2_2") (pintype "passive"))
      (node (ref "U1") (pin "10") (pinfunction "AVIN_10") (pintype "bidirectional"))
      (node (ref "U1") (pin "11") (pinfunction "PVIN_11") (pintype "bidirectional"))
      (node (ref "U1") (pin "12") (pinfunction "PVIN_12") (pintype "bidirectional"))
      (node (ref "U1") (pin "13") (pinfunction "EN_13") (pintype "bidirectional"))
      (node (ref "U16") (pin "9") (pinfunction "BAT_9") (pintype "bidirectional"))
      (node (ref "U18") (pin "5") (pinfunction "VBATT_5") (pintype "bidirectional"))
      (node (ref "U2") (pin "10") (pinfunction "AVIN_10") (pintype "bidirectional"))
      (node (ref "U2") (pin "11") (pinfunction "PVIN_11") (pintype "bidirectional"))
      (node (ref "U2") (pin "12") (pinfunction "PVIN_12") (pintype "bidirectional"))
      (node (ref "U2") (pin "13") (pinfunction "EN_13") (pintype "bidirectional"))
      (node (ref "U28") (pin "2") (pinfunction "IN_2") (pintype "bidirectional"))
      (node (ref "U3") (pin "10") (pinfunction "AVIN_10") (pintype "bidirectional"))
      (node (ref "U3") (pin "11") (pinfunction "PVIN_11") (pintype "bidirectional"))
      (node (ref "U3") (pin "12") (pinfunction "PVIN_12") (pintype "bidirectional"))
      (node (ref "U3") (pin "13") (pinfunction "EN_13") (pintype "bidirectional"))
      (node (ref "U4") (pin "10") (pinfunction "AVIN_10") (pintype "bidirectional"))
      (node (ref "U4") (pin "11") (pinfunction "PVIN_11") (pintype "bidirectional"))
      (node (ref "U4") (pin "12") (pinfunction "PVIN_12") (pintype "bidirectional"))
      (node (ref "U4") (pin "13") (pinfunction "EN_13") (pintype "bidirectional"))
      (node (ref "U5") (pin "10") (pinfunction "AVIN_10") (pintype "bidirectional"))
      (node (ref "U5") (pin "11") (pinfunction "PVIN_11") (pintype "bidirectional"))
      (node (ref "U5") (pin "12") (pinfunction "PVIN_12") (pintype "bidirectional"))
      (node (ref "U5") (pin "13") (pinfunction "EN_13") (pintype "bidirectional"))
    )
    (net (code "75") (name "VBAT-") (class "Default")
      (node (ref "J1") (pin "18") (pinfunction "VBATT-_18") (pintype "power_in"))
      (node (ref "JP1") (pin "3") (pinfunction "3_3") (pintype "passive"))
      (node (ref "R1") (pin "1") (pinfunction "1_1") (pintype "passive"))
      (node (ref "U18") (pin "2") (pinfunction "CSP_2") (pintype "bidirectional"))
    )
    (net (code "76") (name "VBATT_MONITOR_GND") (class "Default")
      (node (ref "C14") (pin "2") (pinfunction "2_2") (pintype "bidirectional"))
      (node (ref "C21") (pin "2") (pinfunction "2_2") (pintype "bidirectional"))
      (node (ref "C22") (pin "2") (pinfunction "2_2") (pintype "bidirectional"))
      (node (ref "C24") (pin "2") (pinfunction "2_2") (pintype "bidirectional"))
      (node (ref "C25") (pin "2") (pinfunction "2_2") (pintype "bidirectional"))
      (node (ref "C26") (pin "2") (pinfunction "2_2") (pintype "bidirectional"))
      (node (ref "C27") (pin "2") (pinfunction "2_2") (pintype "bidirectional"))
      (node (ref "Q1") (pin "3") (pinfunction "S_3") (pintype "passive"))
      (node (ref "R1") (pin "2") (pinfunction "2_2") (pintype "passive"))
      (node (ref "R14") (pin "1") (pinfunction "1_1") (pintype "passive"))
      (node (ref "S1") (pin "1") (pinfunction "A_1") (pintype "bidirectional"))
      (node (ref "U18") (pin "13") (pinfunction "CELLX_13") (pintype "bidirectional"))
      (node (ref "U18") (pin "15") (pinfunction "CSN_15") (pintype "bidirectional"))
      (node (ref "U18") (pin "4") (pinfunction "CSN_4") (pintype "bidirectional"))
      (node (ref "U18") (pin "6") (pinfunction "CELL2_6") (pintype "bidirectional"))
      (node (ref "U18") (pin "7") (pinfunction "CELL1_7") (pintype "bidirectional"))
      (node (ref "U19") (pin "P$1") (pinfunction "GND_P$1") (pintype "bidirectional"))
      (node (ref "U27") (pin "4") (pinfunction "GND_4") (pintype "bidirectional"))
      (node (ref "U28") (pin "3") (pinfunction "GND_3") (pintype "bidirectional"))
      (node (ref "VBATT-M") (pin "TESTPOINT") (pinfunction "TESTPOINT_TESTPOINT") (pintype "bidirectional"))
    )
    (net (code "77") (name "VCC_3V3") (class "Default")
      (node (ref "3V3") (pin "TESTPOINT") (pinfunction "TESTPOINT_TESTPOINT") (pintype "bidirectional"))
      (node (ref "C15") (pin "1") (pinfunction "1_1") (pintype "bidirectional"))
      (node (ref "C46") (pin "2") (pinfunction "2_2") (pintype "bidirectional"))
      (node (ref "R15") (pin "2") (pinfunction "2_2") (pintype "passive"))
      (node (ref "R16") (pin "2") (pinfunction "2_2") (pintype "passive"))
      (node (ref "R17") (pin "2") (pinfunction "2_2") (pintype "passive"))
      (node (ref "R2") (pin "2") (pinfunction "2_2") (pintype "passive"))
      (node (ref "U20") (pin "5") (pinfunction "OUT_5") (pintype "bidirectional"))
      (node (ref "U8") (pin "P1") (pinfunction "SENSE+_P1") (pintype "open_collector"))
    )
    (net (code "78") (name "VCC_5V_1") (class "Default")
      (node (ref "5V_1") (pin "TESTPOINT") (pinfunction "TESTPOINT_TESTPOINT") (pintype "bidirectional"))
      (node (ref "C16") (pin "1") (pinfunction "1_1") (pintype "bidirectional"))
      (node (ref "C47") (pin "2") (pinfunction "2_2") (pintype "bidirectional"))
      (node (ref "R18") (pin "2") (pinfunction "2_2") (pintype "passive"))
      (node (ref "R19") (pin "2") (pinfunction "2_2") (pintype "passive"))
      (node (ref "R20") (pin "2") (pinfunction "2_2") (pintype "passive"))
      (node (ref "R3") (pin "2") (pinfunction "2_2") (pintype "passive"))
      (node (ref "U21") (pin "5") (pinfunction "OUT_5") (pintype "bidirectional"))
      (node (ref "U9") (pin "P1") (pinfunction "SENSE+_P1") (pintype "open_collector"))
    )
    (net (code "79") (name "VCC_5V_2") (class "Default")
      (node (ref "5V_2") (pin "TESTPOINT") (pinfunction "TESTPOINT_TESTPOINT") (pintype "bidirectional"))
      (node (ref "C17") (pin "1") (pinfunction "1_1") (pintype "bidirectional"))
      (node (ref "C48") (pin "2") (pinfunction "2_2") (pintype "bidirectional"))
      (node (ref "R21") (pin "2") (pinfunction "2_2") (pintype "passive"))
      (node (ref "R22") (pin "2") (pinfunction "2_2") (pintype "passive"))
      (node (ref "R23") (pin "2") (pinfunction "2_2") (pintype "passive"))
      (node (ref "R24") (pin "2") (pinfunction "2_2") (pintype "passive"))
      (node (ref "R25") (pin "2") (pinfunction "2_2") (pintype "passive"))
      (node (ref "R26") (pin "2") (pinfunction "2_2") (pintype "passive"))
      (node (ref "R4") (pin "2") (pinfunction "2_2") (pintype "passive"))
      (node (ref "R5") (pin "2") (pinfunction "2_2") (pintype "passive"))
      (node (ref "U10") (pin "P1") (pinfunction "SENSE+_P1") (pintype "open_collector"))
      (node (ref "U11") (pin "P1") (pinfunction "SENSE+_P1") (pintype "open_collector"))
      (node (ref "U22") (pin "5") (pinfunction "OUT_5") (pintype "bidirectional"))
    )
    (net (code "80") (name "VCC_5V_3") (class "Default")
      (node (ref "5V_3") (pin "TESTPOINT") (pinfunction "TESTPOINT_TESTPOINT") (pintype "bidirectional"))
      (node (ref "C18") (pin "1") (pinfunction "1_1") (pintype "bidirectional"))
      (node (ref "C49") (pin "2") (pinfunction "2_2") (pintype "bidirectional"))
      (node (ref "R30") (pin "2") (pinfunction "2_2") (pintype "passive"))
      (node (ref "R31") (pin "2") (pinfunction "2_2") (pintype "passive"))
      (node (ref "R32") (pin "2") (pinfunction "2_2") (pintype "passive"))
      (node (ref "R33") (pin "2") (pinfunction "2_2") (pintype "passive"))
      (node (ref "R34") (pin "2") (pinfunction "2_2") (pintype "passive"))
      (node (ref "R35") (pin "2") (pinfunction "2_2") (pintype "passive"))
      (node (ref "R6") (pin "2") (pinfunction "2_2") (pintype "passive"))
      (node (ref "R7") (pin "2") (pinfunction "2_2") (pintype "passive"))
      (node (ref "U12") (pin "P1") (pinfunction "SENSE+_P1") (pintype "open_collector"))
      (node (ref "U13") (pin "P1") (pinfunction "SENSE+_P1") (pintype "open_collector"))
      (node (ref "U23") (pin "5") (pinfunction "OUT_5") (pintype "bidirectional"))
    )
    (net (code "81") (name "VCC_5V_4") (class "Default")
      (node (ref "5V_4") (pin "TESTPOINT") (pinfunction "TESTPOINT_TESTPOINT") (pintype "bidirectional"))
      (node (ref "C19") (pin "1") (pinfunction "1_1") (pintype "bidirectional"))
      (node (ref "C50") (pin "2") (pinfunction "2_2") (pintype "bidirectional"))
      (node (ref "R27") (pin "2") (pinfunction "2_2") (pintype "passive"))
      (node (ref "R28") (pin "2") (pinfunction "2_2") (pintype "passive"))
      (node (ref "R29") (pin "2") (pinfunction "2_2") (pintype "passive"))
      (node (ref "R36") (pin "2") (pinfunction "2_2") (pintype "passive"))
      (node (ref "R37") (pin "2") (pinfunction "2_2") (pintype "passive"))
      (node (ref "R38") (pin "2") (pinfunction "2_2") (pintype "passive"))
      (node (ref "R8") (pin "2") (pinfunction "2_2") (pintype "passive"))
      (node (ref "R9") (pin "2") (pinfunction "2_2") (pintype "passive"))
      (node (ref "U14") (pin "P1") (pinfunction "SENSE+_P1") (pintype "open_collector"))
      (node (ref "U15") (pin "P1") (pinfunction "SENSE+_P1") (pintype "open_collector"))
      (node (ref "U24") (pin "5") (pinfunction "OUT_5") (pintype "bidirectional"))
    )
    (net (code "82") (name "VCC_BACKPLANE") (class "Default")
      (node (ref "C1") (pin "1") (pinfunction "1_1") (pintype "bidirectional"))
      (node (ref "C23") (pin "1") (pinfunction "1_1") (pintype "bidirectional"))
      (node (ref "J1") (pin "13") (pinfunction "VCC_BACKPLANE_13") (pintype "power_in"))
      (node (ref "J1") (pin "2") (pinfunction "VCC_CONTROLLER_2") (pintype "power_in"))
      (node (ref "J3") (pin "6") (pinfunction "TDO_6") (pintype "bidirectional"))
      (node (ref "R2") (pin "1") (pinfunction "1_1") (pintype "passive"))
      (node (ref "R39") (pin "2") (pinfunction "2_2") (pintype "passive"))
      (node (ref "R40") (pin "2") (pinfunction "2_2") (pintype "passive"))
      (node (ref "R41") (pin "2") (pinfunction "2_2") (pintype "passive"))
      (node (ref "SJ1") (pin "1") (pinfunction "1_1") (pintype "passive"))
      (node (ref "U25") (pin "2") (pinfunction "A1_2") (pintype "bidirectional"))
      (node (ref "U25") (pin "20") (pinfunction "VCC_20") (pintype "bidirectional"))
      (node (ref "U29") (pin "8") (pinfunction "VCC_8") (pintype "bidirectional"))
      (node (ref "U6") (pin "20") (pinfunction "VCC_20") (pintype "bidirectional"))
      (node (ref "U7") (pin "1") (pinfunction "A0_1") (pintype "bidirectional"))
      (node (ref "U7") (pin "20") (pinfunction "VCC_20") (pintype "bidirectional"))
      (node (ref "U8") (pin "P8") (pinfunction "SENSE-_P8") (pintype "open_collector"))
    )
    (net (code "83") (name "VCC_LINUX") (class "Default")
      (node (ref "C2") (pin "1") (pinfunction "1_1") (pintype "bidirectional"))
      (node (ref "J1") (pin "4") (pinfunction "VCC_LINUX_4") (pintype "power_in"))
      (node (ref "R3") (pin "1") (pinfunction "1_1") (pintype "passive"))
      (node (ref "U9") (pin "P8") (pinfunction "SENSE-_P8") (pintype "open_collector"))
    )
    (net (code "84") (name "VCC_MOD0") (class "Default")
      (node (ref "C3") (pin "1") (pinfunction "1_1") (pintype "bidirectional"))
      (node (ref "J1") (pin "7") (pinfunction "VCC_MOD0_7") (pintype "power_in"))
      (node (ref "R4") (pin "1") (pinfunction "1_1") (pintype "passive"))
      (node (ref "U10") (pin "P8") (pinfunction "SENSE-_P8") (pintype "open_collector"))
    )
    (net (code "85") (name "VCC_MOD1") (class "Default")
      (node (ref "C4") (pin "1") (pinfunction "1_1") (pintype "bidirectional"))
      (node (ref "J1") (pin "8") (pinfunction "VCC_MOD1_8") (pintype "power_in"))
      (node (ref "R5") (pin "1") (pinfunction "1_1") (pintype "passive"))
      (node (ref "U11") (pin "P8") (pinfunction "SENSE-_P8") (pintype "open_collector"))
    )
    (net (code "86") (name "VCC_MOD2") (class "Default")
      (node (ref "C5") (pin "1") (pinfunction "1_1") (pintype "bidirectional"))
      (node (ref "J1") (pin "9") (pinfunction "VCC_MOD2_9") (pintype "power_in"))
      (node (ref "R6") (pin "1") (pinfunction "1_1") (pintype "passive"))
      (node (ref "U12") (pin "P8") (pinfunction "SENSE-_P8") (pintype "open_collector"))
    )
    (net (code "87") (name "VCC_MOD5") (class "Default")
      (node (ref "C6") (pin "1") (pinfunction "1_1") (pintype "bidirectional"))
      (node (ref "J1") (pin "10") (pinfunction "VCC_MOD5_10") (pintype "power_in"))
      (node (ref "R7") (pin "1") (pinfunction "1_1") (pintype "passive"))
      (node (ref "U13") (pin "P8") (pinfunction "SENSE-_P8") (pintype "open_collector"))
    )
    (net (code "88") (name "VCC_MOD6") (class "Default")
      (node (ref "C7") (pin "1") (pinfunction "1_1") (pintype "bidirectional"))
      (node (ref "J1") (pin "11") (pinfunction "VCC_MOD6_11") (pintype "power_in"))
      (node (ref "R8") (pin "1") (pinfunction "1_1") (pintype "passive"))
      (node (ref "U14") (pin "P8") (pinfunction "SENSE-_P8") (pintype "open_collector"))
    )
    (net (code "89") (name "VCC_MOD7") (class "Default")
      (node (ref "C8") (pin "1") (pinfunction "1_1") (pintype "bidirectional"))
      (node (ref "J1") (pin "12") (pinfunction "VCC_MOD7_12") (pintype "power_in"))
      (node (ref "R9") (pin "1") (pinfunction "1_1") (pintype "passive"))
      (node (ref "U15") (pin "P8") (pinfunction "SENSE-_P8") (pintype "open_collector"))
    )
    (net (code "90") (name "VSOL+") (class "Default")
      (node (ref "C20") (pin "1") (pinfunction "1_1") (pintype "bidirectional"))
      (node (ref "J1") (pin "19") (pinfunction "VSOL+_19") (pintype "power_in"))
      (node (ref "JP1") (pin "2") (pinfunction "2_2") (pintype "passive"))
      (node (ref "R11") (pin "2") (pinfunction "2_2") (pintype "passive"))
      (node (ref "U26") (pin "P1") (pinfunction "SENSE+_P1") (pintype "open_collector"))
    )
    (net (code "91") (name "VSOL_SENSE") (class "Default")
      (node (ref "C40") (pin "P$1") (pinfunction "1_P$1") (pintype "bidirectional"))
      (node (ref "R11") (pin "1") (pinfunction "1_1") (pintype "passive"))
      (node (ref "R55") (pin "2") (pinfunction "2_2") (pintype "passive"))
      (node (ref "U16") (pin "1") (pinfunction "VIN_1") (pintype "bidirectional"))
      (node (ref "U16") (pin "3") (pinfunction "~{SHDN}_3") (pintype "bidirectional"))
      (node (ref "U17") (pin "4") (pinfunction "V+_4") (pintype "bidirectional"))
      (node (ref "U26") (pin "P8") (pinfunction "SENSE-_P8") (pintype "open_collector"))
    )
    (net (code "92") (name "WDI") (class "Default")
      (node (ref "J1") (pin "16") (pinfunction "WDI_16") (pintype "power_in"))
      (node (ref "U27") (pin "6") (pinfunction "WDI_6") (pintype "bidirectional"))
    )
    (net (code "93") (name "unconnected-(J3-TCK-Pad4)") (class "Default")
      (node (ref "J3") (pin "4") (pinfunction "TCK_4") (pintype "bidirectional"))
    )
    (net (code "94") (name "unconnected-(J3-TMS-Pad2)") (class "Default")
      (node (ref "J3") (pin "2") (pinfunction "TMS_2") (pintype "bidirectional"))
    )
    (net (code "95") (name "unconnected-(U16-NTC-Pad8)") (class "Default")
      (node (ref "U16") (pin "8") (pinfunction "NTC_8") (pintype "bidirectional"))
    )
    (net (code "96") (name "unconnected-(U16-~{CHRG}-Pad4)") (class "Default")
      (node (ref "U16") (pin "4") (pinfunction "~{CHRG}_4") (pintype "bidirectional"))
    )
    (net (code "97") (name "unconnected-(U16-~{FAULT}-Pad5)") (class "Default")
      (node (ref "U16") (pin "5") (pinfunction "~{FAULT}_5") (pintype "bidirectional"))
    )
    (net (code "98") (name "unconnected-(U18-AIN1-Pad9)") (class "Default")
      (node (ref "U18") (pin "9") (pinfunction "AIN1_9") (pintype "bidirectional"))
    )
    (net (code "99") (name "unconnected-(U18-AIN2-Pad10)") (class "Default")
      (node (ref "U18") (pin "10") (pinfunction "AIN2_10") (pintype "bidirectional"))
    )
    (net (code "100") (name "unconnected-(U18-THRM-Pad14)") (class "Default")
      (node (ref "U18") (pin "14") (pinfunction "THRM_14") (pintype "bidirectional"))
    )
    (net (code "101") (name "unconnected-(U20-FLG-Pad4)") (class "Default")
      (node (ref "U20") (pin "4") (pinfunction "FLG_4") (pintype "bidirectional"))
    )
    (net (code "102") (name "unconnected-(U21-FLG-Pad4)") (class "Default")
      (node (ref "U21") (pin "4") (pinfunction "FLG_4") (pintype "bidirectional"))
    )
    (net (code "103") (name "unconnected-(U22-FLG-Pad4)") (class "Default")
      (node (ref "U22") (pin "4") (pinfunction "FLG_4") (pintype "bidirectional"))
    )
    (net (code "104") (name "unconnected-(U23-FLG-Pad4)") (class "Default")
      (node (ref "U23") (pin "4") (pinfunction "FLG_4") (pintype "bidirectional"))
    )
    (net (code "105") (name "unconnected-(U24-FLG-Pad4)") (class "Default")
      (node (ref "U24") (pin "4") (pinfunction "FLG_4") (pintype "bidirectional"))
    )
    (net (code "106") (name "unconnected-(U25-SC1-Pad9)") (class "Default")
      (node (ref "U25") (pin "9") (pinfunction "SC1_9") (pintype "bidirectional"))
    )
    (net (code "107") (name "unconnected-(U25-SC2-Pad13)") (class "Default")
      (node (ref "U25") (pin "13") (pinfunction "SC2_13") (pintype "bidirectional"))
    )
    (net (code "108") (name "unconnected-(U25-SC3-Pad16)") (class "Default")
      (node (ref "U25") (pin "16") (pinfunction "SC3_16") (pintype "bidirectional"))
    )
    (net (code "109") (name "unconnected-(U25-SD1-Pad8)") (class "Default")
      (node (ref "U25") (pin "8") (pinfunction "SD1_8") (pintype "bidirectional"))
    )
    (net (code "110") (name "unconnected-(U25-SD2-Pad12)") (class "Default")
      (node (ref "U25") (pin "12") (pinfunction "SD2_12") (pintype "bidirectional"))
    )
    (net (code "111") (name "unconnected-(U25-SD3-Pad15)") (class "Default")
      (node (ref "U25") (pin "15") (pinfunction "SD3_15") (pintype "bidirectional"))
    )
    (net (code "112") (name "unconnected-(U25-~{INT1}-Pad7)") (class "Default")
      (node (ref "U25") (pin "7") (pinfunction "~{INT1}_7") (pintype "bidirectional"))
    )
    (net (code "113") (name "unconnected-(U25-~{INT2}-Pad11)") (class "Default")
      (node (ref "U25") (pin "11") (pinfunction "~{INT2}_11") (pintype "bidirectional"))
    )
    (net (code "114") (name "unconnected-(U25-~{INT3}-Pad14)") (class "Default")
      (node (ref "U25") (pin "14") (pinfunction "~{INT3}_14") (pintype "bidirectional"))
    )
    (net (code "115") (name "~{INT}") (class "Default")
      (node (ref "J1") (pin "6") (pinfunction "~{SMBALERT}_6") (pintype "bidirectional"))
      (node (ref "R53") (pin "2") (pinfunction "2_2") (pintype "passive"))
      (node (ref "U25") (pin "17") (pinfunction "~{INT}_17") (pintype "bidirectional"))
      (node (ref "U6") (pin "17") (pinfunction "~{INT}_17") (pintype "bidirectional"))
      (node (ref "U7") (pin "17") (pinfunction "~{INT}_17") (pintype "bidirectional"))
    )
  )
)
